# Nixie_Test.net
KiCad netlist of a schematic drawn in EAGLE
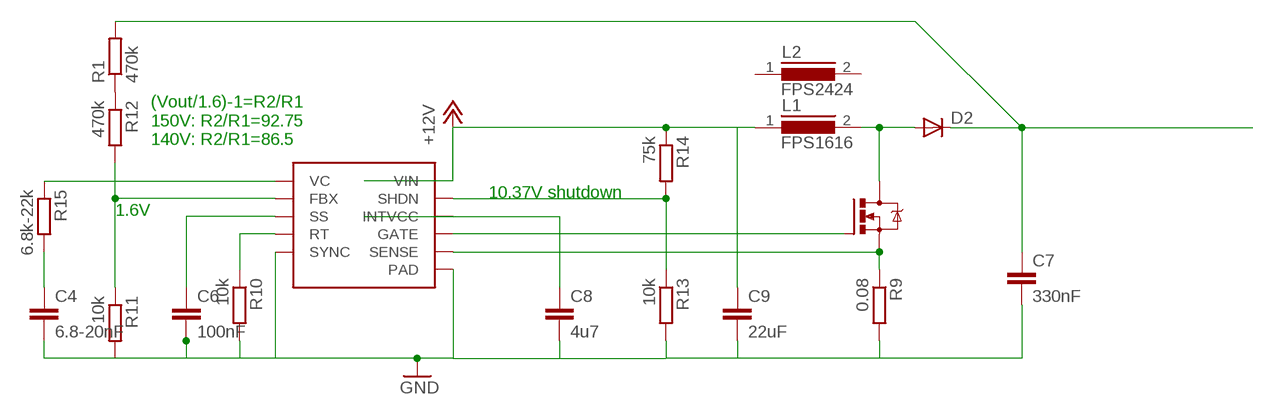
[diagram p0: schematic, sheet 1]
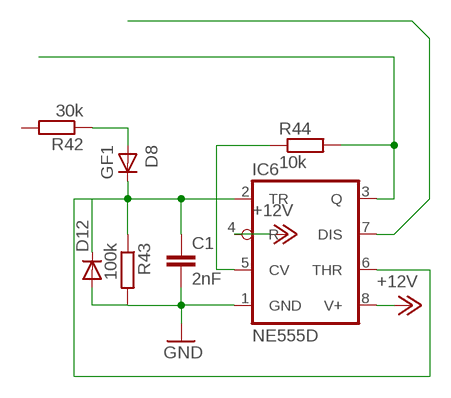
[diagram p1: schematic, sheet 2]
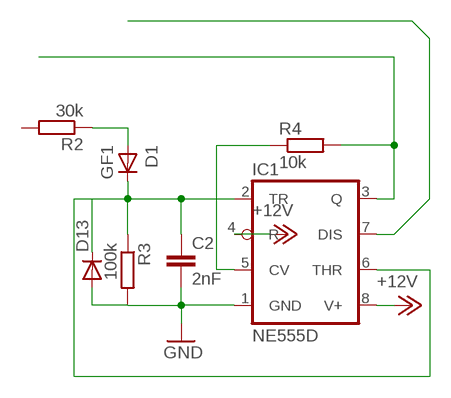
[diagram p2: schematic, sheet 3]
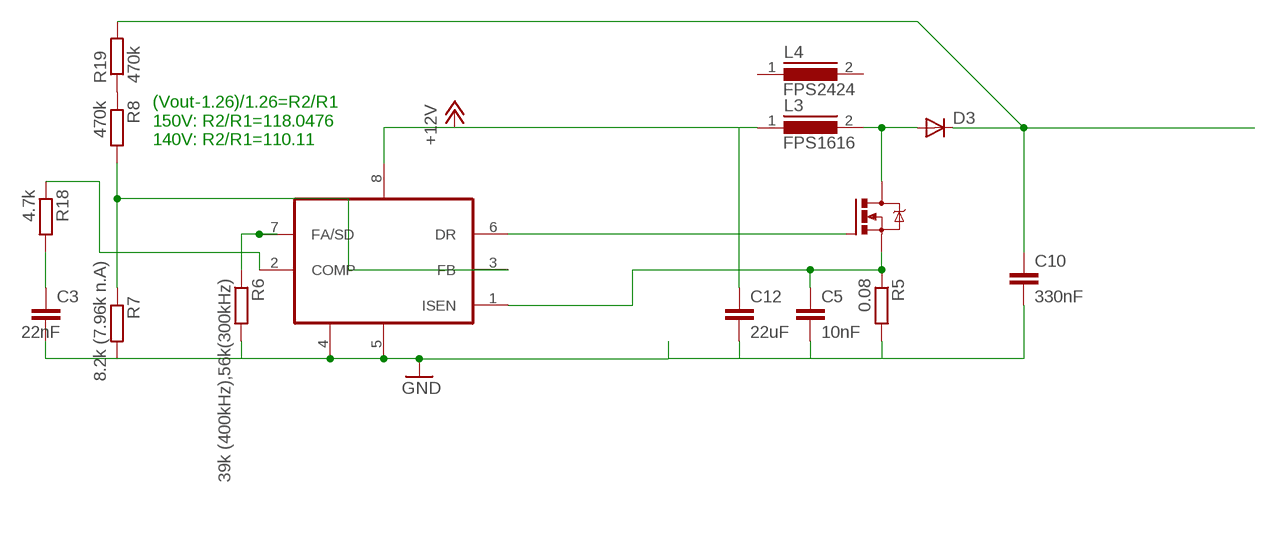
[diagram p3: schematic, sheet 4]
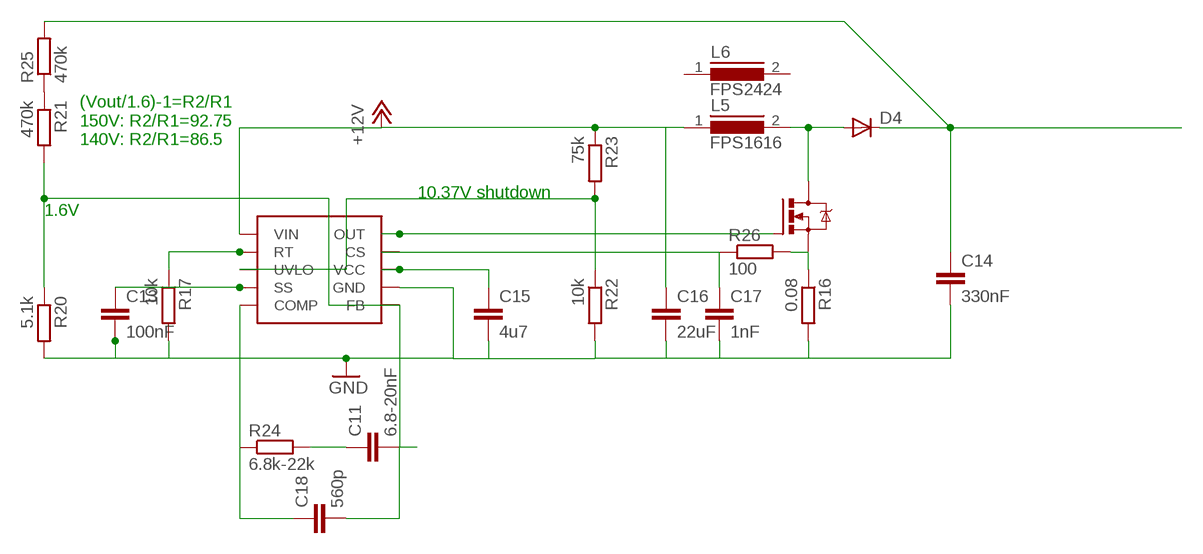
[diagram p4: schematic, sheet 5]
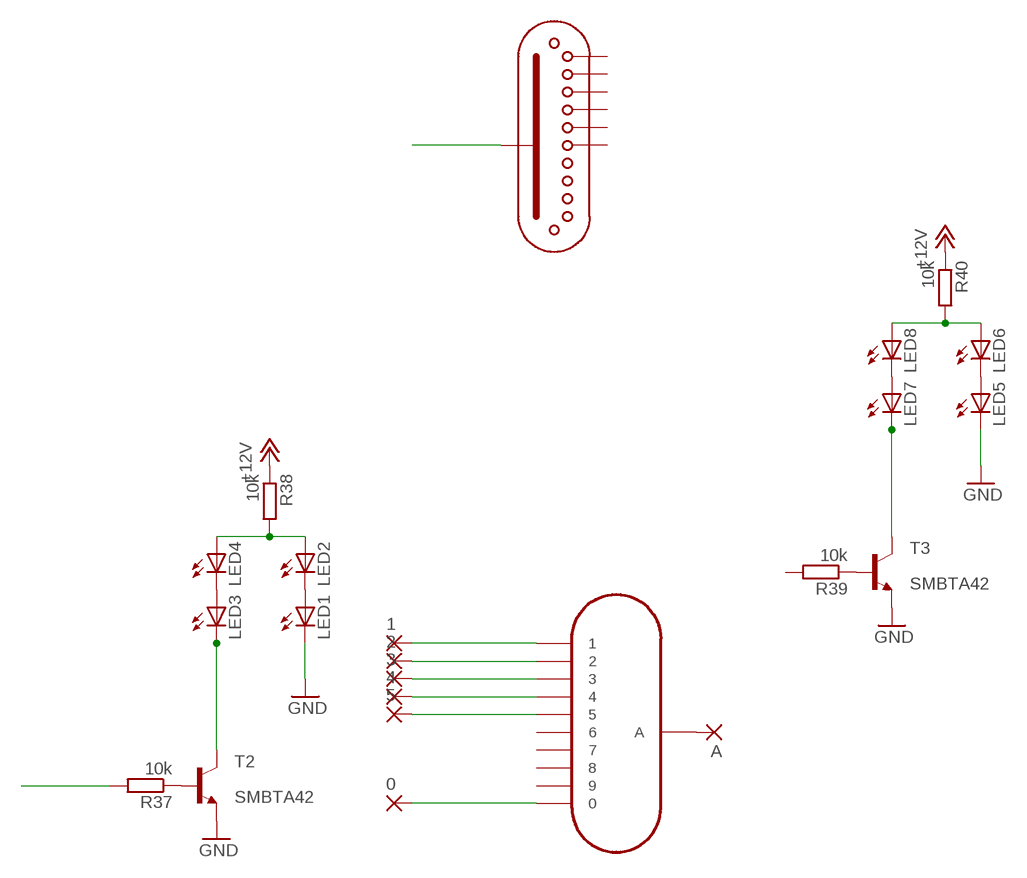
[diagram p5: schematic, sheet 6]
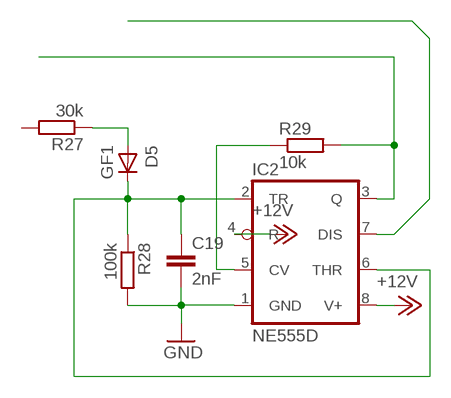
[diagram p6: schematic, sheet 7]
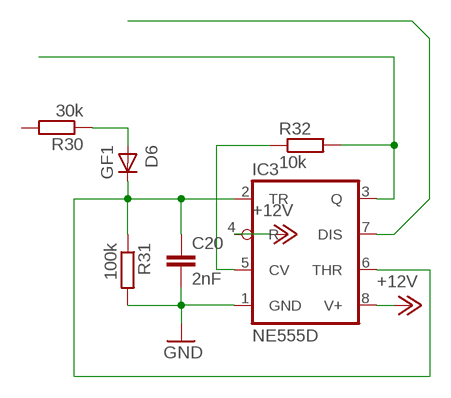
[diagram p7: schematic, sheet 8]
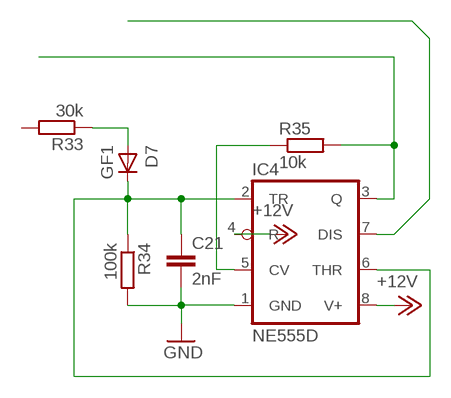
[diagram p8: schematic, sheet 9]
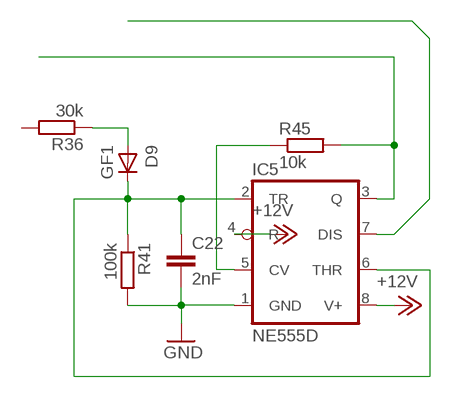
[diagram p9: schematic, sheet 10]
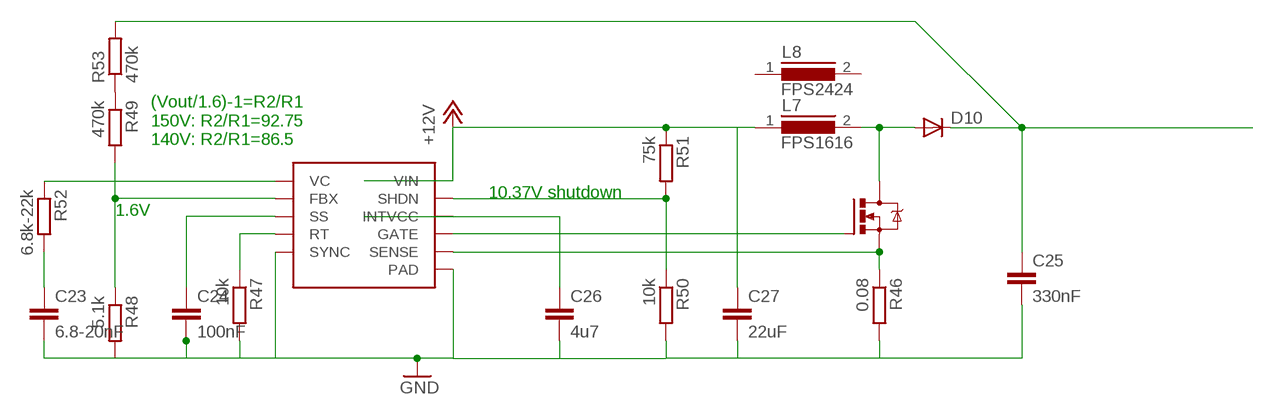
[diagram p10: schematic, sheet 11]
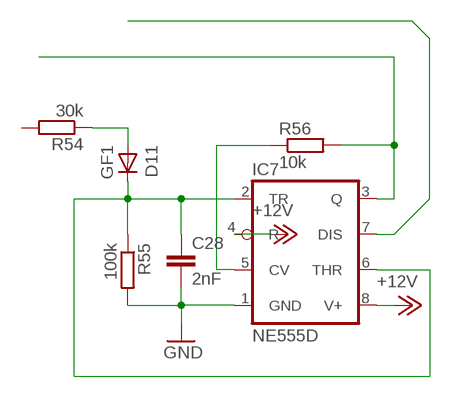
[diagram p11: schematic, sheet 12]
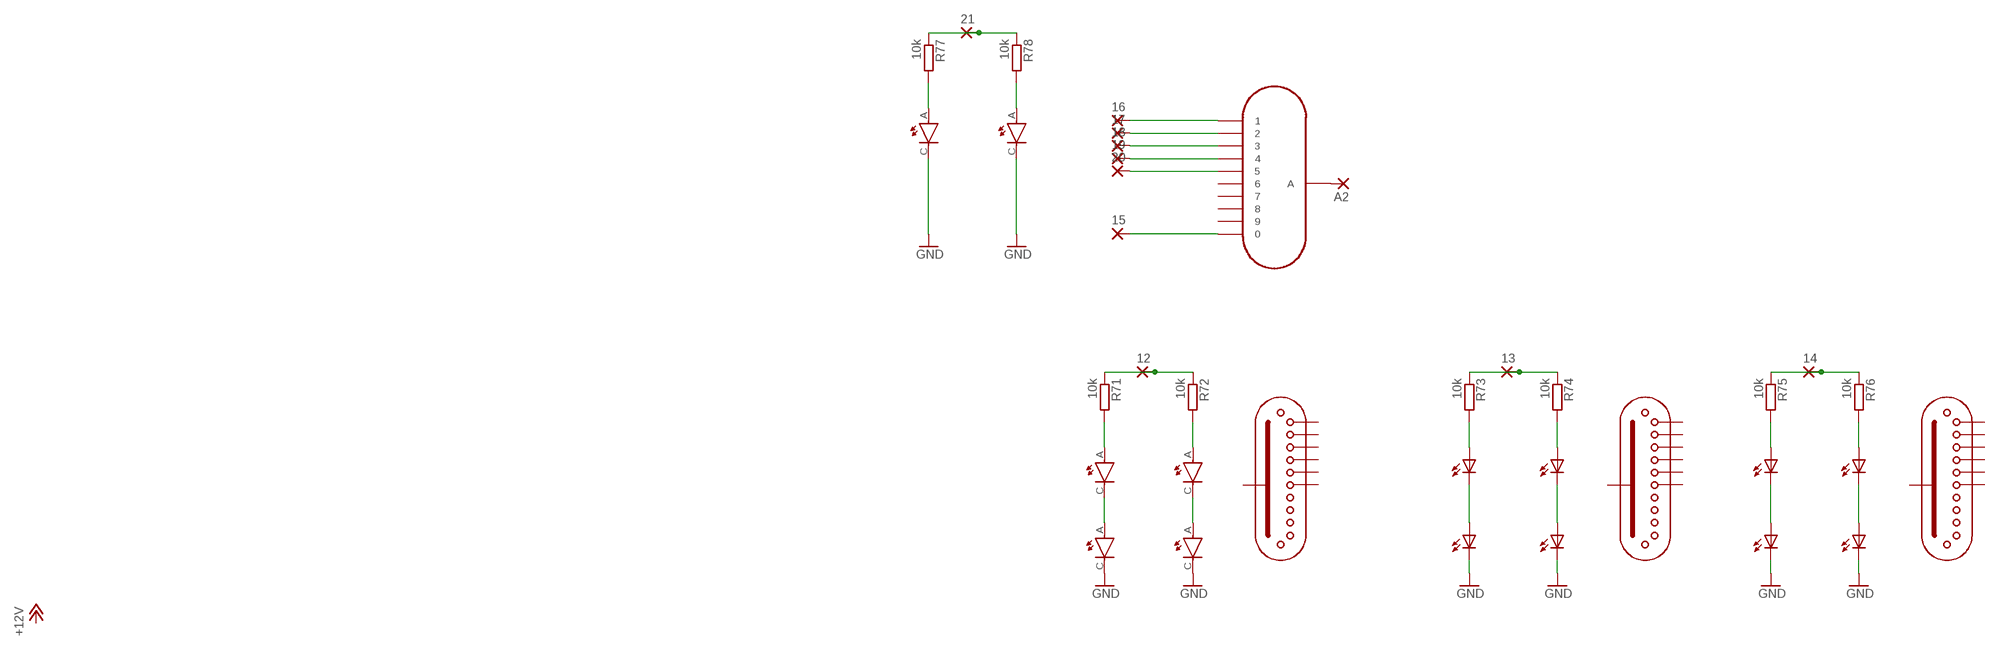
[diagram p12: schematic, sheet 13]
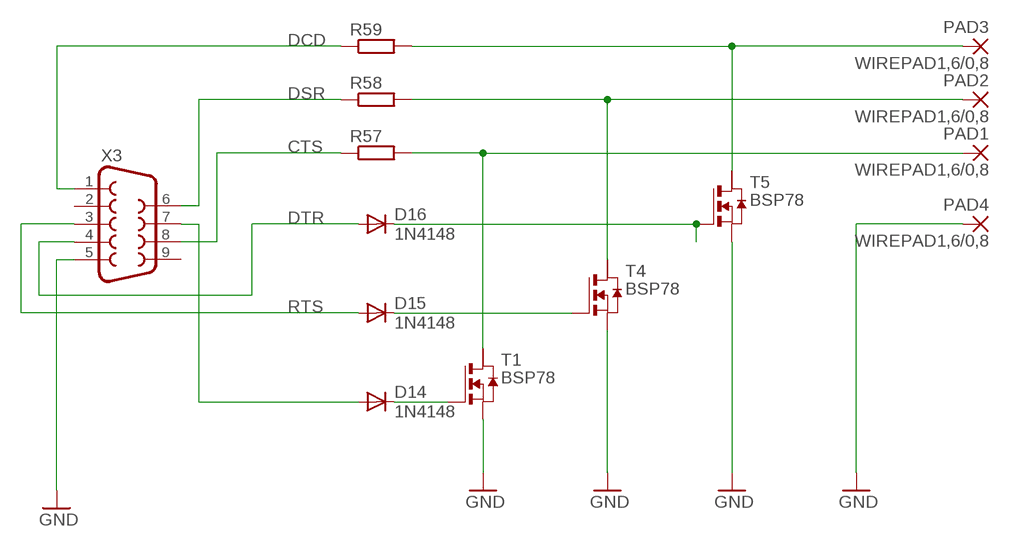
[diagram p13: schematic, sheet 14]
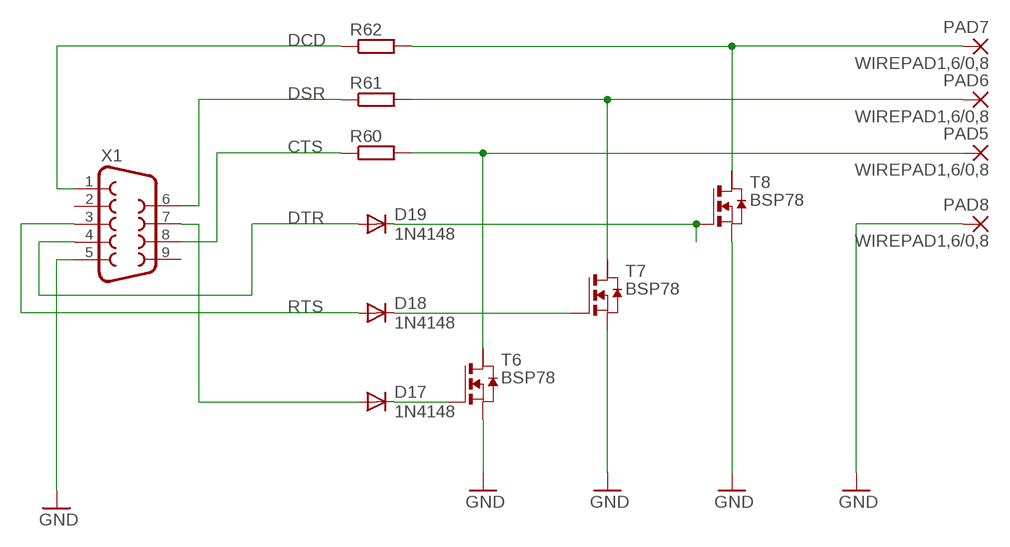
[diagram p14: schematic, sheet 15]
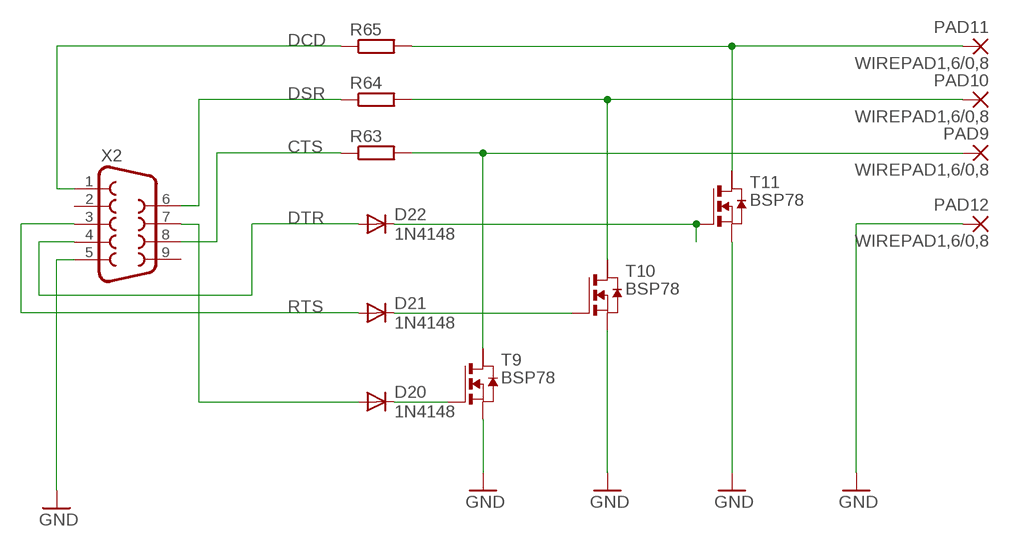
[diagram p15: schematic, sheet 16]
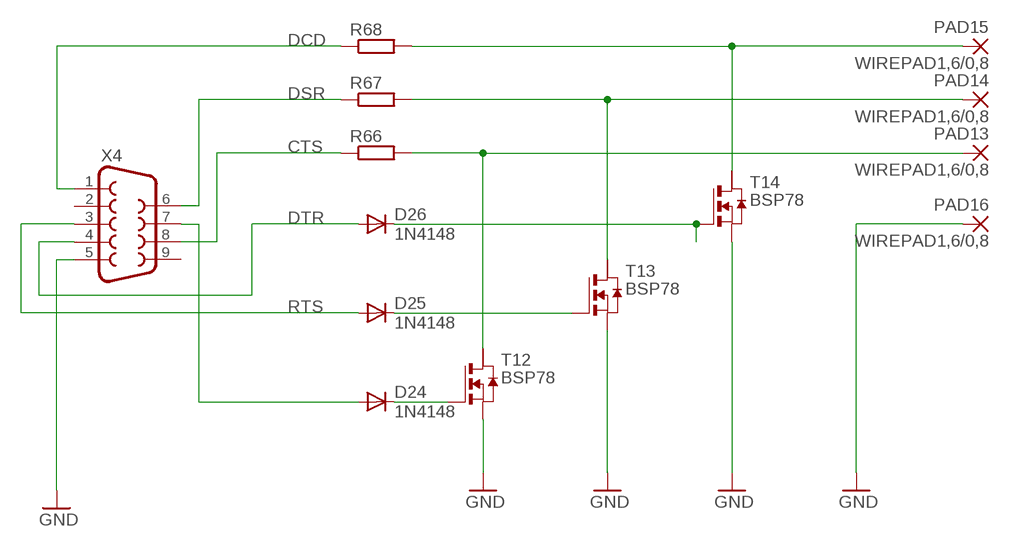
[diagram p16: schematic, sheet 17]

(export (version "E")
  (design (tool "Eeschema 10.0.6"))
  (components
    (comp (ref "C2")
      (value "2nF")
      (footprint "eagle-import:C1206K")
      (libsource (lib "eagle-import") (part "C-EUC1206K"))
    )
    (comp (ref "D1")
      (value "GF1")
      (footprint "eagle-import:SMA-DO214AC")
      (libsource (lib "eagle-import") (part "GF1"))
    )
    (comp (ref "D13")
      (value "DIODE-DO214AA")
      (footprint "eagle-import:DO214AA")
      (libsource (lib "eagle-import") (part "DIODE-DO214AA"))
    )
    (comp (ref "IC1")
      (value "NE555D")
      (footprint "eagle-import:SO08")
      (libsource (lib "eagle-import") (part "555DNE"))
    )
    (comp (ref "R2")
      (value "30k")
      (footprint "eagle-import:R0805")
      (libsource (lib "eagle-import") (part "R-EU_R0805"))
    )
    (comp (ref "R3")
      (value "100k")
      (footprint "eagle-import:R0805")
      (libsource (lib "eagle-import") (part "R-EU_R0805"))
    )
    (comp (ref "R4")
      (value "10k")
      (footprint "eagle-import:R0805")
      (libsource (lib "eagle-import") (part "R-EU_R0805"))
    )
    (comp (ref "C28")
      (value "2nF")
      (footprint "eagle-import:C1206K")
      (libsource (lib "eagle-import") (part "C-EUC1206K"))
    )
    (comp (ref "D11")
      (value "GF1")
      (footprint "eagle-import:SMA-DO214AC")
      (libsource (lib "eagle-import") (part "GF1"))
    )
    (comp (ref "IC7")
      (value "NE555D")
      (footprint "eagle-import:SO08")
      (libsource (lib "eagle-import") (part "555DNE"))
    )
    (comp (ref "R54")
      (value "30k")
      (footprint "eagle-import:R0805")
      (libsource (lib "eagle-import") (part "R-EU_R0805"))
    )
    (comp (ref "R55")
      (value "100k")
      (footprint "eagle-import:R0805")
      (libsource (lib "eagle-import") (part "R-EU_R0805"))
    )
    (comp (ref "R56")
      (value "10k")
      (footprint "eagle-import:R0805")
      (libsource (lib "eagle-import") (part "R-EU_R0805"))
    )
    (comp (ref "D14")
      (value "1N4148")
      (footprint "eagle-import:SOD323-W")
      (libsource (lib "eagle-import") (part "DIODE-SOD323-W"))
    )
    (comp (ref "D15")
      (value "1N4148")
      (footprint "eagle-import:SOD323-W")
      (libsource (lib "eagle-import") (part "DIODE-SOD323-W"))
    )
    (comp (ref "D16")
      (value "1N4148")
      (footprint "eagle-import:SOD323-W")
      (libsource (lib "eagle-import") (part "DIODE-SOD323-W"))
    )
    (comp (ref "PAD1")
      (value "WIREPAD1,6/0,8")
      (footprint "eagle-import:1,6_0,8")
      (libsource (lib "eagle-import") (part "WIREPAD1,6/0,8"))
    )
    (comp (ref "PAD2")
      (value "WIREPAD1,6/0,8")
      (footprint "eagle-import:1,6_0,8")
      (libsource (lib "eagle-import") (part "WIREPAD1,6/0,8"))
    )
    (comp (ref "PAD3")
      (value "WIREPAD1,6/0,8")
      (footprint "eagle-import:1,6_0,8")
      (libsource (lib "eagle-import") (part "WIREPAD1,6/0,8"))
    )
    (comp (ref "PAD4")
      (value "WIREPAD1,6/0,8")
      (footprint "eagle-import:1,6_0,8")
      (libsource (lib "eagle-import") (part "WIREPAD1,6/0,8"))
    )
    (comp (ref "R57")
      (value "R-EU_R0805")
      (footprint "eagle-import:R0805")
      (libsource (lib "eagle-import") (part "R-EU_R0805"))
    )
    (comp (ref "R58")
      (value "R-EU_R0805")
      (footprint "eagle-import:R0805")
      (libsource (lib "eagle-import") (part "R-EU_R0805"))
    )
    (comp (ref "R59")
      (value "R-EU_R0805")
      (footprint "eagle-import:R0805")
      (libsource (lib "eagle-import") (part "R-EU_R0805"))
    )
    (comp (ref "T1")
      (value "BSP78")
      (footprint "eagle-import:SOT223")
      (libsource (lib "eagle-import") (part "NMOSSOT223"))
    )
    (comp (ref "T4")
      (value "BSP78")
      (footprint "eagle-import:SOT223")
      (libsource (lib "eagle-import") (part "NMOSSOT223"))
    )
    (comp (ref "T5")
      (value "BSP78")
      (footprint "eagle-import:SOT223")
      (libsource (lib "eagle-import") (part "NMOSSOT223"))
    )
    (comp (ref "X3")
      (value "F09D")
      (footprint "eagle-import:F09D")
      (libsource (lib "eagle-import") (part "F09D"))
    )
    (comp (ref "12")
      (value "SMD2")
      (footprint "eagle-import:SMD1,27-2,54")
      (libsource (lib "eagle-import") (part "SMD2"))
    )
    (comp (ref "13")
      (value "SMD2")
      (footprint "eagle-import:SMD1,27-2,54")
      (libsource (lib "eagle-import") (part "SMD2"))
    )
    (comp (ref "14")
      (value "SMD2")
      (footprint "eagle-import:SMD1,27-2,54")
      (libsource (lib "eagle-import") (part "SMD2"))
    )
    (comp (ref "15")
      (value "SMD2")
      (footprint "eagle-import:SMD1,27-2,54")
      (libsource (lib "eagle-import") (part "SMD2"))
    )
    (comp (ref "16")
      (value "SMD2")
      (footprint "eagle-import:SMD1,27-2,54")
      (libsource (lib "eagle-import") (part "SMD2"))
    )
    (comp (ref "17")
      (value "SMD2")
      (footprint "eagle-import:SMD1,27-2,54")
      (libsource (lib "eagle-import") (part "SMD2"))
    )
    (comp (ref "18")
      (value "SMD2")
      (footprint "eagle-import:SMD1,27-2,54")
      (libsource (lib "eagle-import") (part "SMD2"))
    )
    (comp (ref "19")
      (value "SMD2")
      (footprint "eagle-import:SMD1,27-2,54")
      (libsource (lib "eagle-import") (part "SMD2"))
    )
    (comp (ref "20")
      (value "SMD2")
      (footprint "eagle-import:SMD1,27-2,54")
      (libsource (lib "eagle-import") (part "SMD2"))
    )
    (comp (ref "21")
      (value "SMD2")
      (footprint "eagle-import:SMD1,27-2,54")
      (libsource (lib "eagle-import") (part "SMD2"))
    )
    (comp (ref "A2")
      (value "SMD2")
      (footprint "eagle-import:SMD1,27-2,54")
      (libsource (lib "eagle-import") (part "SMD2"))
    )
    (comp (ref "LED17")
      (value "LED_PLCC6")
      (footprint "eagle-import:PLCC6")
      (libsource (lib "eagle-import") (part "LED_PLCC6"))
    )
    (comp (ref "LED18")
      (value "LED_PLCC6")
      (footprint "eagle-import:PLCC6")
      (libsource (lib "eagle-import") (part "LED_PLCC6"))
    )
    (comp (ref "LED19")
      (value "LED_PLCC6")
      (footprint "eagle-import:PLCC6")
      (libsource (lib "eagle-import") (part "LED_PLCC6"))
    )
    (comp (ref "LED20")
      (value "LED_PLCC6")
      (footprint "eagle-import:PLCC6")
      (libsource (lib "eagle-import") (part "LED_PLCC6"))
    )
    (comp (ref "LED21")
      (value "LED_LRTB_G6TG")
      (footprint "eagle-import:PLCC6")
      (libsource (lib "eagle-import") (part "LED_LRTB_G6TG"))
    )
    (comp (ref "LED22")
      (value "LED_LRTB_G6TG")
      (footprint "eagle-import:PLCC6")
      (libsource (lib "eagle-import") (part "LED_LRTB_G6TG"))
    )
    (comp (ref "N3")
      (value "IN-12A-IN-12")
      (footprint "eagle-import:IN-12")
      (libsource (lib "eagle-import") (part "IN-12A-IN-12"))
    )
    (comp (ref "R71")
      (value "10k")
      (footprint "eagle-import:R0805")
      (libsource (lib "eagle-import") (part "R-EU_R0805"))
    )
    (comp (ref "R72")
      (value "10k")
      (footprint "eagle-import:R0805")
      (libsource (lib "eagle-import") (part "R-EU_R0805"))
    )
    (comp (ref "R73")
      (value "10k")
      (footprint "eagle-import:R0805")
      (libsource (lib "eagle-import") (part "R-EU_R0805"))
    )
    (comp (ref "R74")
      (value "10k")
      (footprint "eagle-import:R0805")
      (libsource (lib "eagle-import") (part "R-EU_R0805"))
    )
    (comp (ref "R75")
      (value "10k")
      (footprint "eagle-import:R0805")
      (libsource (lib "eagle-import") (part "R-EU_R0805"))
    )
    (comp (ref "R76")
      (value "10k")
      (footprint "eagle-import:R0805")
      (libsource (lib "eagle-import") (part "R-EU_R0805"))
    )
    (comp (ref "R77")
      (value "10k")
      (footprint "eagle-import:R0805")
      (libsource (lib "eagle-import") (part "R-EU_R0805"))
    )
    (comp (ref "R78")
      (value "10k")
      (footprint "eagle-import:R0805")
      (libsource (lib "eagle-import") (part "R-EU_R0805"))
    )
    (comp (ref "U$5")
      (value "PLCC2")
      (footprint "eagle-import:PLCC2")
      (libsource (lib "eagle-import") (part "PLCC2"))
    )
    (comp (ref "U$6")
      (value "PLCC2")
      (footprint "eagle-import:PLCC2")
      (libsource (lib "eagle-import") (part "PLCC2"))
    )
    (comp (ref "U$7")
      (value "ZM1020")
      (footprint "eagle-import:ZM1020")
      (libsource (lib "eagle-import") (part "ZM1020"))
    )
    (comp (ref "U$8")
      (value "PLCC2")
      (footprint "eagle-import:PLCC2")
      (libsource (lib "eagle-import") (part "PLCC2"))
    )
    (comp (ref "U$9")
      (value "PLCC2")
      (footprint "eagle-import:PLCC2")
      (libsource (lib "eagle-import") (part "PLCC2"))
    )
    (comp (ref "U$10")
      (value "ZM1020")
      (footprint "eagle-import:ZM1020")
      (libsource (lib "eagle-import") (part "ZM1020"))
    )
    (comp (ref "U$11")
      (value "ZM1020")
      (footprint "eagle-import:ZM1020")
      (libsource (lib "eagle-import") (part "ZM1020"))
    )
    (comp (ref "U$12")
      (value "PLCC2")
      (footprint "eagle-import:PLCC2")
      (libsource (lib "eagle-import") (part "PLCC2"))
    )
    (comp (ref "U$13")
      (value "PLCC2")
      (footprint "eagle-import:PLCC2")
      (libsource (lib "eagle-import") (part "PLCC2"))
    )
    (comp (ref "C21")
      (value "2nF")
      (footprint "eagle-import:C1206K")
      (libsource (lib "eagle-import") (part "C-EUC1206K"))
    )
    (comp (ref "D7")
      (value "GF1")
      (footprint "eagle-import:SMA-DO214AC")
      (libsource (lib "eagle-import") (part "GF1"))
    )
    (comp (ref "IC4")
      (value "NE555D")
      (footprint "eagle-import:SO08")
      (libsource (lib "eagle-import") (part "555DNE"))
    )
    (comp (ref "R33")
      (value "30k")
      (footprint "eagle-import:R0805")
      (libsource (lib "eagle-import") (part "R-EU_R0805"))
    )
    (comp (ref "R34")
      (value "100k")
      (footprint "eagle-import:R0805")
      (libsource (lib "eagle-import") (part "R-EU_R0805"))
    )
    (comp (ref "R35")
      (value "10k")
      (footprint "eagle-import:R0805")
      (libsource (lib "eagle-import") (part "R-EU_R0805"))
    )
    (comp (ref "C1")
      (value "2nF")
      (footprint "eagle-import:C1206K")
      (libsource (lib "eagle-import") (part "C-EUC1206K"))
    )
    (comp (ref "D8")
      (value "GF1")
      (footprint "eagle-import:SMA-DO214AC")
      (libsource (lib "eagle-import") (part "GF1"))
    )
    (comp (ref "D12")
      (value "DIODE-DO214AA")
      (footprint "eagle-import:DO214AA")
      (libsource (lib "eagle-import") (part "DIODE-DO214AA"))
    )
    (comp (ref "IC6")
      (value "NE555D")
      (footprint "eagle-import:SO08")
      (libsource (lib "eagle-import") (part "555DNE"))
    )
    (comp (ref "R42")
      (value "30k")
      (footprint "eagle-import:R0805")
      (libsource (lib "eagle-import") (part "R-EU_R0805"))
    )
    (comp (ref "R43")
      (value "100k")
      (footprint "eagle-import:R0805")
      (libsource (lib "eagle-import") (part "R-EU_R0805"))
    )
    (comp (ref "R44")
      (value "10k")
      (footprint "eagle-import:R0805")
      (libsource (lib "eagle-import") (part "R-EU_R0805"))
    )
    (comp (ref "C4")
      (value "6.8-20nF")
      (footprint "eagle-import:C0805K")
      (libsource (lib "eagle-import") (part "C-EUC0805K"))
    )
    (comp (ref "C6")
      (value "100nF")
      (footprint "eagle-import:C0805K")
      (libsource (lib "eagle-import") (part "C-EUC0805K"))
    )
    (comp (ref "C7")
      (value "330nF")
      (footprint "eagle-import:C1812")
      (libsource (lib "eagle-import") (part "C-EUC1812"))
    )
    (comp (ref "C8")
      (value "4u7")
      (footprint "eagle-import:C1206K")
      (libsource (lib "eagle-import") (part "C-EUC1206K"))
    )
    (comp (ref "C9")
      (value "22uF")
      (footprint "eagle-import:C1210K")
      (libsource (lib "eagle-import") (part "C-EUC1210K"))
    )
    (comp (ref "D2")
      (value "DIODE-DO219AB")
      (footprint "eagle-import:DO219AB")
      (libsource (lib "eagle-import") (part "DIODE-DO219AB"))
    )
    (comp (ref "L1")
      (value "FPS1616")
      (footprint "eagle-import:1616FPS_22UH")
      (libsource (lib "eagle-import") (part "FPS1616"))
    )
    (comp (ref "L2")
      (value "FPS2424")
      (footprint "eagle-import:242408FPS_22UH")
      (libsource (lib "eagle-import") (part "FPS2424"))
    )
    (comp (ref "Q1")
      (value "N-MOSFET-TO252-DPAK")
      (footprint "eagle-import:TO252")
      (libsource (lib "eagle-import") (part "N-MOSFET-TO252-DPAK"))
    )
    (comp (ref "R1")
      (value "470k")
      (footprint "eagle-import:R0805")
      (libsource (lib "eagle-import") (part "R-EU_R0805"))
    )
    (comp (ref "R9")
      (value "0.08")
      (footprint "eagle-import:R0805")
      (libsource (lib "eagle-import") (part "R-EU_R0805"))
    )
    (comp (ref "R10")
      (value "10k")
      (footprint "eagle-import:R0805")
      (libsource (lib "eagle-import") (part "R-EU_R0805"))
    )
    (comp (ref "R11")
      (value "10k")
      (footprint "eagle-import:R0805")
      (libsource (lib "eagle-import") (part "R-EU_R0805"))
    )
    (comp (ref "R12")
      (value "470k")
      (footprint "eagle-import:R0805")
      (libsource (lib "eagle-import") (part "R-EU_R0805"))
    )
    (comp (ref "R13")
      (value "10k")
      (footprint "eagle-import:R0805")
      (libsource (lib "eagle-import") (part "R-EU_R0805"))
    )
    (comp (ref "R14")
      (value "75k")
      (footprint "eagle-import:R0805")
      (libsource (lib "eagle-import") (part "R-EU_R0805"))
    )
    (comp (ref "R15")
      (value "6.8k-22k")
      (footprint "eagle-import:R0805")
      (libsource (lib "eagle-import") (part "R-EU_R0805"))
    )
    (comp (ref "U2")
      (value "LT3757MSOP-10")
      (footprint "eagle-import:MSOP-10")
      (libsource (lib "eagle-import") (part "LT3757MSOP-10"))
    )
    (comp (ref "D17")
      (value "1N4148")
      (footprint "eagle-import:SOD323-W")
      (libsource (lib "eagle-import") (part "DIODE-SOD323-W"))
    )
    (comp (ref "D18")
      (value "1N4148")
      (footprint "eagle-import:SOD323-W")
      (libsource (lib "eagle-import") (part "DIODE-SOD323-W"))
    )
    (comp (ref "D19")
      (value "1N4148")
      (footprint "eagle-import:SOD323-W")
      (libsource (lib "eagle-import") (part "DIODE-SOD323-W"))
    )
    (comp (ref "PAD5")
      (value "WIREPAD1,6/0,8")
      (footprint "eagle-import:1,6_0,8")
      (libsource (lib "eagle-import") (part "WIREPAD1,6/0,8"))
    )
    (comp (ref "PAD6")
      (value "WIREPAD1,6/0,8")
      (footprint "eagle-import:1,6_0,8")
      (libsource (lib "eagle-import") (part "WIREPAD1,6/0,8"))
    )
    (comp (ref "PAD7")
      (value "WIREPAD1,6/0,8")
      (footprint "eagle-import:1,6_0,8")
      (libsource (lib "eagle-import") (part "WIREPAD1,6/0,8"))
    )
    (comp (ref "PAD8")
      (value "WIREPAD1,6/0,8")
      (footprint "eagle-import:1,6_0,8")
      (libsource (lib "eagle-import") (part "WIREPAD1,6/0,8"))
    )
    (comp (ref "R60")
      (value "R-EU_R0805")
      (footprint "eagle-import:R0805")
      (libsource (lib "eagle-import") (part "R-EU_R0805"))
    )
    (comp (ref "R61")
      (value "R-EU_R0805")
      (footprint "eagle-import:R0805")
      (libsource (lib "eagle-import") (part "R-EU_R0805"))
    )
    (comp (ref "R62")
      (value "R-EU_R0805")
      (footprint "eagle-import:R0805")
      (libsource (lib "eagle-import") (part "R-EU_R0805"))
    )
    (comp (ref "T6")
      (value "BSP78")
      (footprint "eagle-import:SOT223")
      (libsource (lib "eagle-import") (part "NMOSSOT223"))
    )
    (comp (ref "T7")
      (value "BSP78")
      (footprint "eagle-import:SOT223")
      (libsource (lib "eagle-import") (part "NMOSSOT223"))
    )
    (comp (ref "T8")
      (value "BSP78")
      (footprint "eagle-import:SOT223")
      (libsource (lib "eagle-import") (part "NMOSSOT223"))
    )
    (comp (ref "X1")
      (value "F09D")
      (footprint "eagle-import:F09D")
      (libsource (lib "eagle-import") (part "F09D"))
    )
    (comp (ref "D24")
      (value "1N4148")
      (footprint "eagle-import:SOD323-W")
      (libsource (lib "eagle-import") (part "DIODE-SOD323-W"))
    )
    (comp (ref "D25")
      (value "1N4148")
      (footprint "eagle-import:SOD323-W")
      (libsource (lib "eagle-import") (part "DIODE-SOD323-W"))
    )
    (comp (ref "D26")
      (value "1N4148")
      (footprint "eagle-import:SOD323-W")
      (libsource (lib "eagle-import") (part "DIODE-SOD323-W"))
    )
    (comp (ref "PAD13")
      (value "WIREPAD1,6/0,8")
      (footprint "eagle-import:1,6_0,8")
      (libsource (lib "eagle-import") (part "WIREPAD1,6/0,8"))
    )
    (comp (ref "PAD14")
      (value "WIREPAD1,6/0,8")
      (footprint "eagle-import:1,6_0,8")
      (libsource (lib "eagle-import") (part "WIREPAD1,6/0,8"))
    )
    (comp (ref "PAD15")
      (value "WIREPAD1,6/0,8")
      (footprint "eagle-import:1,6_0,8")
      (libsource (lib "eagle-import") (part "WIREPAD1,6/0,8"))
    )
    (comp (ref "PAD16")
      (value "WIREPAD1,6/0,8")
      (footprint "eagle-import:1,6_0,8")
      (libsource (lib "eagle-import") (part "WIREPAD1,6/0,8"))
    )
    (comp (ref "R66")
      (value "R-EU_R0805")
      (footprint "eagle-import:R0805")
      (libsource (lib "eagle-import") (part "R-EU_R0805"))
    )
    (comp (ref "R67")
      (value "R-EU_R0805")
      (footprint "eagle-import:R0805")
      (libsource (lib "eagle-import") (part "R-EU_R0805"))
    )
    (comp (ref "R68")
      (value "R-EU_R0805")
      (footprint "eagle-import:R0805")
      (libsource (lib "eagle-import") (part "R-EU_R0805"))
    )
    (comp (ref "T12")
      (value "BSP78")
      (footprint "eagle-import:SOT223")
      (libsource (lib "eagle-import") (part "NMOSSOT223"))
    )
    (comp (ref "T13")
      (value "BSP78")
      (footprint "eagle-import:SOT223")
      (libsource (lib "eagle-import") (part "NMOSSOT223"))
    )
    (comp (ref "T14")
      (value "BSP78")
      (footprint "eagle-import:SOT223")
      (libsource (lib "eagle-import") (part "NMOSSOT223"))
    )
    (comp (ref "X4")
      (value "F09D")
      (footprint "eagle-import:F09D")
      (libsource (lib "eagle-import") (part "F09D"))
    )
    (comp (ref "C23")
      (value "6.8-20nF")
      (footprint "eagle-import:C0805K")
      (libsource (lib "eagle-import") (part "C-EUC0805K"))
    )
    (comp (ref "C24")
      (value "100nF")
      (footprint "eagle-import:C0805K")
      (libsource (lib "eagle-import") (part "C-EUC0805K"))
    )
    (comp (ref "C25")
      (value "330nF")
      (footprint "eagle-import:C1812")
      (libsource (lib "eagle-import") (part "C-EUC1812"))
    )
    (comp (ref "C26")
      (value "4u7")
      (footprint "eagle-import:C1206K")
      (libsource (lib "eagle-import") (part "C-EUC1206K"))
    )
    (comp (ref "C27")
      (value "22uF")
      (footprint "eagle-import:C1210K")
      (libsource (lib "eagle-import") (part "C-EUC1210K"))
    )
    (comp (ref "D10")
      (value "DIODE-DO219AB")
      (footprint "eagle-import:DO219AB")
      (libsource (lib "eagle-import") (part "DIODE-DO219AB"))
    )
    (comp (ref "L7")
      (value "FPS1616")
      (footprint "eagle-import:1616FPS_22UH")
      (libsource (lib "eagle-import") (part "FPS1616"))
    )
    (comp (ref "L8")
      (value "FPS2424")
      (footprint "eagle-import:242408FPS_22UH")
      (libsource (lib "eagle-import") (part "FPS2424"))
    )
    (comp (ref "Q4")
      (value "N-MOSFET-TO252-DPAK")
      (footprint "eagle-import:TO252")
      (libsource (lib "eagle-import") (part "N-MOSFET-TO252-DPAK"))
    )
    (comp (ref "R46")
      (value "0.08")
      (footprint "eagle-import:R0805")
      (libsource (lib "eagle-import") (part "R-EU_R0805"))
    )
    (comp (ref "R47")
      (value "10k")
      (footprint "eagle-import:R0805")
      (libsource (lib "eagle-import") (part "R-EU_R0805"))
    )
    (comp (ref "R48")
      (value "5.1k")
      (footprint "eagle-import:R0805")
      (libsource (lib "eagle-import") (part "R-EU_R0805"))
    )
    (comp (ref "R49")
      (value "470k")
      (footprint "eagle-import:R0805")
      (libsource (lib "eagle-import") (part "R-EU_R0805"))
    )
    (comp (ref "R50")
      (value "10k")
      (footprint "eagle-import:R0805")
      (libsource (lib "eagle-import") (part "R-EU_R0805"))
    )
    (comp (ref "R51")
      (value "75k")
      (footprint "eagle-import:R0805")
      (libsource (lib "eagle-import") (part "R-EU_R0805"))
    )
    (comp (ref "R52")
      (value "6.8k-22k")
      (footprint "eagle-import:R0805")
      (libsource (lib "eagle-import") (part "R-EU_R0805"))
    )
    (comp (ref "R53")
      (value "470k")
      (footprint "eagle-import:R0805")
      (libsource (lib "eagle-import") (part "R-EU_R0805"))
    )
    (comp (ref "U1")
      (value "LT3757MSOP-10")
      (footprint "eagle-import:MSOP-10")
      (libsource (lib "eagle-import") (part "LT3757MSOP-10"))
    )
    (comp (ref "C20")
      (value "2nF")
      (footprint "eagle-import:C1206K")
      (libsource (lib "eagle-import") (part "C-EUC1206K"))
    )
    (comp (ref "D6")
      (value "GF1")
      (footprint "eagle-import:SMA-DO214AC")
      (libsource (lib "eagle-import") (part "GF1"))
    )
    (comp (ref "IC3")
      (value "NE555D")
      (footprint "eagle-import:SO08")
      (libsource (lib "eagle-import") (part "555DNE"))
    )
    (comp (ref "R30")
      (value "30k")
      (footprint "eagle-import:R0805")
      (libsource (lib "eagle-import") (part "R-EU_R0805"))
    )
    (comp (ref "R31")
      (value "100k")
      (footprint "eagle-import:R0805")
      (libsource (lib "eagle-import") (part "R-EU_R0805"))
    )
    (comp (ref "R32")
      (value "10k")
      (footprint "eagle-import:R0805")
      (libsource (lib "eagle-import") (part "R-EU_R0805"))
    )
    (comp (ref "C22")
      (value "2nF")
      (footprint "eagle-import:C1206K")
      (libsource (lib "eagle-import") (part "C-EUC1206K"))
    )
    (comp (ref "D9")
      (value "GF1")
      (footprint "eagle-import:SMA-DO214AC")
      (libsource (lib "eagle-import") (part "GF1"))
    )
    (comp (ref "IC5")
      (value "NE555D")
      (footprint "eagle-import:SO08")
      (libsource (lib "eagle-import") (part "555DNE"))
    )
    (comp (ref "R36")
      (value "30k")
      (footprint "eagle-import:R0805")
      (libsource (lib "eagle-import") (part "R-EU_R0805"))
    )
    (comp (ref "R41")
      (value "100k")
      (footprint "eagle-import:R0805")
      (libsource (lib "eagle-import") (part "R-EU_R0805"))
    )
    (comp (ref "R45")
      (value "10k")
      (footprint "eagle-import:R0805")
      (libsource (lib "eagle-import") (part "R-EU_R0805"))
    )
    (comp (ref "C3")
      (value "22nF")
      (footprint "eagle-import:C0805K")
      (libsource (lib "eagle-import") (part "C-EUC0805K"))
    )
    (comp (ref "C5")
      (value "10nF")
      (footprint "eagle-import:C0805K")
      (libsource (lib "eagle-import") (part "C-EUC0805K"))
    )
    (comp (ref "C10")
      (value "330nF")
      (footprint "eagle-import:C1812")
      (libsource (lib "eagle-import") (part "C-EUC1812"))
    )
    (comp (ref "C12")
      (value "22uF")
      (footprint "eagle-import:C1210K")
      (libsource (lib "eagle-import") (part "C-EUC1210K"))
    )
    (comp (ref "D3")
      (value "DIODE-DO219AB")
      (footprint "eagle-import:DO219AB")
      (libsource (lib "eagle-import") (part "DIODE-DO219AB"))
    )
    (comp (ref "L3")
      (value "FPS1616")
      (footprint "eagle-import:1616FPS_22UH")
      (libsource (lib "eagle-import") (part "FPS1616"))
    )
    (comp (ref "L4")
      (value "FPS2424")
      (footprint "eagle-import:242408FPS_22UH")
      (libsource (lib "eagle-import") (part "FPS2424"))
    )
    (comp (ref "Q2")
      (value "N-MOSFET-TO252-DPAK")
      (footprint "eagle-import:TO252")
      (libsource (lib "eagle-import") (part "N-MOSFET-TO252-DPAK"))
    )
    (comp (ref "R5")
      (value "0.08")
      (footprint "eagle-import:R0805")
      (libsource (lib "eagle-import") (part "R-EU_R0805"))
    )
    (comp (ref "R6")
      (value "39k (400kHz),56k(300kHz)")
      (footprint "eagle-import:R0805")
      (libsource (lib "eagle-import") (part "R-EU_R0805"))
    )
    (comp (ref "R7")
      (value "8.2k (7.96k n.A)")
      (footprint "eagle-import:R0805")
      (libsource (lib "eagle-import") (part "R-EU_R0805"))
    )
    (comp (ref "R8")
      (value "470k")
      (footprint "eagle-import:R0805")
      (libsource (lib "eagle-import") (part "R-EU_R0805"))
    )
    (comp (ref "R18")
      (value "4.7k")
      (footprint "eagle-import:R0805")
      (libsource (lib "eagle-import") (part "R-EU_R0805"))
    )
    (comp (ref "R19")
      (value "470k")
      (footprint "eagle-import:R0805")
      (libsource (lib "eagle-import") (part "R-EU_R0805"))
    )
    (comp (ref "U3")
      (value "LM3478")
      (footprint "eagle-import:MSOP08")
      (libsource (lib "eagle-import") (part "LM3478"))
    )
    (comp (ref "C11")
      (value "6.8-20nF")
      (footprint "eagle-import:C0805K")
      (libsource (lib "eagle-import") (part "C-EUC0805K"))
    )
    (comp (ref "C13")
      (value "100nF")
      (footprint "eagle-import:C0805K")
      (libsource (lib "eagle-import") (part "C-EUC0805K"))
    )
    (comp (ref "C14")
      (value "330nF")
      (footprint "eagle-import:C1812")
      (libsource (lib "eagle-import") (part "C-EUC1812"))
    )
    (comp (ref "C15")
      (value "4u7")
      (footprint "eagle-import:C1206K")
      (libsource (lib "eagle-import") (part "C-EUC1206K"))
    )
    (comp (ref "C16")
      (value "22uF")
      (footprint "eagle-import:C1210K")
      (libsource (lib "eagle-import") (part "C-EUC1210K"))
    )
    (comp (ref "C17")
      (value "1nF")
      (footprint "eagle-import:C0805K")
      (libsource (lib "eagle-import") (part "C-EUC0805K"))
    )
    (comp (ref "C18")
      (value "560p")
      (footprint "eagle-import:C0805K")
      (libsource (lib "eagle-import") (part "C-EUC0805K"))
    )
    (comp (ref "D4")
      (value "DIODE-DO219AB")
      (footprint "eagle-import:DO219AB")
      (libsource (lib "eagle-import") (part "DIODE-DO219AB"))
    )
    (comp (ref "L5")
      (value "FPS1616")
      (footprint "eagle-import:1616FPS_22UH")
      (libsource (lib "eagle-import") (part "FPS1616"))
    )
    (comp (ref "L6")
      (value "FPS2424")
      (footprint "eagle-import:242408FPS_22UH")
      (libsource (lib "eagle-import") (part "FPS2424"))
    )
    (comp (ref "Q3")
      (value "N-MOSFET-TO252-DPAK")
      (footprint "eagle-import:TO252")
      (libsource (lib "eagle-import") (part "N-MOSFET-TO252-DPAK"))
    )
    (comp (ref "R16")
      (value "0.08")
      (footprint "eagle-import:R0805")
      (libsource (lib "eagle-import") (part "R-EU_R0805"))
    )
    (comp (ref "R17")
      (value "10k")
      (footprint "eagle-import:R0805")
      (libsource (lib "eagle-import") (part "R-EU_R0805"))
    )
    (comp (ref "R20")
      (value "5.1k")
      (footprint "eagle-import:R0805")
      (libsource (lib "eagle-import") (part "R-EU_R0805"))
    )
    (comp (ref "R21")
      (value "470k")
      (footprint "eagle-import:R0805")
      (libsource (lib "eagle-import") (part "R-EU_R0805"))
    )
    (comp (ref "R22")
      (value "10k")
      (footprint "eagle-import:R0805")
      (libsource (lib "eagle-import") (part "R-EU_R0805"))
    )
    (comp (ref "R23")
      (value "75k")
      (footprint "eagle-import:R0805")
      (libsource (lib "eagle-import") (part "R-EU_R0805"))
    )
    (comp (ref "R24")
      (value "6.8k-22k")
      (footprint "eagle-import:R0805")
      (libsource (lib "eagle-import") (part "R-EU_R0805"))
    )
    (comp (ref "R25")
      (value "470k")
      (footprint "eagle-import:R0805")
      (libsource (lib "eagle-import") (part "R-EU_R0805"))
    )
    (comp (ref "R26")
      (value "100")
      (footprint "eagle-import:R0805")
      (libsource (lib "eagle-import") (part "R-EU_R0805"))
    )
    (comp (ref "U4")
      (value "LM5022MSOP-10")
      (footprint "eagle-import:MSOP-10-NOPAD")
      (libsource (lib "eagle-import") (part "LM5022MSOP-10"))
    )
    (comp (ref "D20")
      (value "1N4148")
      (footprint "eagle-import:SOD323-W")
      (libsource (lib "eagle-import") (part "DIODE-SOD323-W"))
    )
    (comp (ref "D21")
      (value "1N4148")
      (footprint "eagle-import:SOD323-W")
      (libsource (lib "eagle-import") (part "DIODE-SOD323-W"))
    )
    (comp (ref "D22")
      (value "1N4148")
      (footprint "eagle-import:SOD323-W")
      (libsource (lib "eagle-import") (part "DIODE-SOD323-W"))
    )
    (comp (ref "PAD9")
      (value "WIREPAD1,6/0,8")
      (footprint "eagle-import:1,6_0,8")
      (libsource (lib "eagle-import") (part "WIREPAD1,6/0,8"))
    )
    (comp (ref "PAD10")
      (value "WIREPAD1,6/0,8")
      (footprint "eagle-import:1,6_0,8")
      (libsource (lib "eagle-import") (part "WIREPAD1,6/0,8"))
    )
    (comp (ref "PAD11")
      (value "WIREPAD1,6/0,8")
      (footprint "eagle-import:1,6_0,8")
      (libsource (lib "eagle-import") (part "WIREPAD1,6/0,8"))
    )
    (comp (ref "PAD12")
      (value "WIREPAD1,6/0,8")
      (footprint "eagle-import:1,6_0,8")
      (libsource (lib "eagle-import") (part "WIREPAD1,6/0,8"))
    )
    (comp (ref "R63")
      (value "R-EU_R0805")
      (footprint "eagle-import:R0805")
      (libsource (lib "eagle-import") (part "R-EU_R0805"))
    )
    (comp (ref "R64")
      (value "R-EU_R0805")
      (footprint "eagle-import:R0805")
      (libsource (lib "eagle-import") (part "R-EU_R0805"))
    )
    (comp (ref "R65")
      (value "R-EU_R0805")
      (footprint "eagle-import:R0805")
      (libsource (lib "eagle-import") (part "R-EU_R0805"))
    )
    (comp (ref "T9")
      (value "BSP78")
      (footprint "eagle-import:SOT223")
      (libsource (lib "eagle-import") (part "NMOSSOT223"))
    )
    (comp (ref "T10")
      (value "BSP78")
      (footprint "eagle-import:SOT223")
      (libsource (lib "eagle-import") (part "NMOSSOT223"))
    )
    (comp (ref "T11")
      (value "BSP78")
      (footprint "eagle-import:SOT223")
      (libsource (lib "eagle-import") (part "NMOSSOT223"))
    )
    (comp (ref "X2")
      (value "F09D")
      (footprint "eagle-import:F09D")
      (libsource (lib "eagle-import") (part "F09D"))
    )
    (comp (ref "C19")
      (value "2nF")
      (footprint "eagle-import:C1206K")
      (libsource (lib "eagle-import") (part "C-EUC1206K"))
    )
    (comp (ref "D5")
      (value "GF1")
      (footprint "eagle-import:SMA-DO214AC")
      (libsource (lib "eagle-import") (part "GF1"))
    )
    (comp (ref "IC2")
      (value "NE555D")
      (footprint "eagle-import:SO08")
      (libsource (lib "eagle-import") (part "555DNE"))
    )
    (comp (ref "R27")
      (value "30k")
      (footprint "eagle-import:R0805")
      (libsource (lib "eagle-import") (part "R-EU_R0805"))
    )
    (comp (ref "R28")
      (value "100k")
      (footprint "eagle-import:R0805")
      (libsource (lib "eagle-import") (part "R-EU_R0805"))
    )
    (comp (ref "R29")
      (value "10k")
      (footprint "eagle-import:R0805")
      (libsource (lib "eagle-import") (part "R-EU_R0805"))
    )
    (comp (ref "0")
      (value "SMD2")
      (footprint "eagle-import:SMD1,27-2,54")
      (libsource (lib "eagle-import") (part "SMD2"))
    )
    (comp (ref "1")
      (value "SMD2")
      (footprint "eagle-import:SMD1,27-2,54")
      (libsource (lib "eagle-import") (part "SMD2"))
    )
    (comp (ref "2")
      (value "SMD2")
      (footprint "eagle-import:SMD1,27-2,54")
      (libsource (lib "eagle-import") (part "SMD2"))
    )
    (comp (ref "3")
      (value "SMD2")
      (footprint "eagle-import:SMD1,27-2,54")
      (libsource (lib "eagle-import") (part "SMD2"))
    )
    (comp (ref "4")
      (value "SMD2")
      (footprint "eagle-import:SMD1,27-2,54")
      (libsource (lib "eagle-import") (part "SMD2"))
    )
    (comp (ref "5")
      (value "SMD2")
      (footprint "eagle-import:SMD1,27-2,54")
      (libsource (lib "eagle-import") (part "SMD2"))
    )
    (comp (ref "A")
      (value "SMD2")
      (footprint "eagle-import:SMD1,27-2,54")
      (libsource (lib "eagle-import") (part "SMD2"))
    )
    (comp (ref "LED1")
      (value "LED3MM")
      (footprint "eagle-import:LED3MM")
      (libsource (lib "eagle-import") (part "LED3MM"))
    )
    (comp (ref "LED2")
      (value "LED3MM")
      (footprint "eagle-import:LED3MM")
      (libsource (lib "eagle-import") (part "LED3MM"))
    )
    (comp (ref "LED3")
      (value "LED3MM")
      (footprint "eagle-import:LED3MM")
      (libsource (lib "eagle-import") (part "LED3MM"))
    )
    (comp (ref "LED4")
      (value "LED3MM")
      (footprint "eagle-import:LED3MM")
      (libsource (lib "eagle-import") (part "LED3MM"))
    )
    (comp (ref "LED5")
      (value "LED3MM")
      (footprint "eagle-import:LED3MM")
      (libsource (lib "eagle-import") (part "LED3MM"))
    )
    (comp (ref "LED6")
      (value "LED3MM")
      (footprint "eagle-import:LED3MM")
      (libsource (lib "eagle-import") (part "LED3MM"))
    )
    (comp (ref "LED7")
      (value "LED3MM")
      (footprint "eagle-import:LED3MM")
      (libsource (lib "eagle-import") (part "LED3MM"))
    )
    (comp (ref "LED8")
      (value "LED3MM")
      (footprint "eagle-import:LED3MM")
      (libsource (lib "eagle-import") (part "LED3MM"))
    )
    (comp (ref "N1")
      (value "IN-12A-IN-12")
      (footprint "eagle-import:IN-12")
      (libsource (lib "eagle-import") (part "IN-12A-IN-12"))
    )
    (comp (ref "R37")
      (value "10k")
      (footprint "eagle-import:R0805")
      (libsource (lib "eagle-import") (part "R-EU_R0805"))
    )
    (comp (ref "R38")
      (value "10k")
      (footprint "eagle-import:R0805")
      (libsource (lib "eagle-import") (part "R-EU_R0805"))
    )
    (comp (ref "R39")
      (value "10k")
      (footprint "eagle-import:R0805")
      (libsource (lib "eagle-import") (part "R-EU_R0805"))
    )
    (comp (ref "R40")
      (value "10k")
      (footprint "eagle-import:R0805")
      (libsource (lib "eagle-import") (part "R-EU_R0805"))
    )
    (comp (ref "T2")
      (value "MMBTA42LT1-NPN-SOT23-BEC")
      (footprint "eagle-import:SOT23-BEC")
      (fields (field (name "T") "SMBTA42"))
      (libsource (lib "eagle-import") (part "-NPN-SOT23-BECMMBTA42LT1"))
    )
    (comp (ref "T3")
      (value "MMBTA42LT1-NPN-SOT23-BEC")
      (footprint "eagle-import:SOT23-BEC")
      (fields (field (name "T") "SMBTA42"))
      (libsource (lib "eagle-import") (part "-NPN-SOT23-BECMMBTA42LT1"))
    )
    (comp (ref "U$3")
      (value "ZM1020")
      (footprint "eagle-import:ZM1020")
      (libsource (lib "eagle-import") (part "ZM1020"))
    )
  )
  (nets
    (net (code "1") (name "+12V") (class "Default")
      (node (ref "C12") (pin "1") (pinfunction "1_1") (pintype "passive"))
      (node (ref "C16") (pin "1") (pinfunction "1_1") (pintype "passive"))
      (node (ref "C27") (pin "1") (pinfunction "1_1") (pintype "passive"))
      (node (ref "C9") (pin "1") (pinfunction "1_1") (pintype "passive"))
      (node (ref "IC1") (pin "4") (pinfunction "R_4") (pintype "input"))
      (node (ref "IC1") (pin "8") (pinfunction "V+_8") (pintype "power_in"))
      (node (ref "IC2") (pin "4") (pinfunction "R_4") (pintype "input"))
      (node (ref "IC2") (pin "8") (pinfunction "V+_8") (pintype "power_in"))
      (node (ref "IC3") (pin "4") (pinfunction "R_4") (pintype "input"))
      (node (ref "IC3") (pin "8") (pinfunction "V+_8") (pintype "power_in"))
      (node (ref "IC4") (pin "4") (pinfunction "R_4") (pintype "input"))
      (node (ref "IC4") (pin "8") (pinfunction "V+_8") (pintype "power_in"))
      (node (ref "IC5") (pin "4") (pinfunction "R_4") (pintype "input"))
      (node (ref "IC5") (pin "8") (pinfunction "V+_8") (pintype "power_in"))
      (node (ref "IC6") (pin "4") (pinfunction "R_4") (pintype "input"))
      (node (ref "IC6") (pin "8") (pinfunction "V+_8") (pintype "power_in"))
      (node (ref "IC7") (pin "4") (pinfunction "R_4") (pintype "input"))
      (node (ref "IC7") (pin "8") (pinfunction "V+_8") (pintype "power_in"))
      (node (ref "L1") (pin "1") (pinfunction "1_1") (pintype "passive"))
      (node (ref "L3") (pin "1") (pinfunction "1_1") (pintype "passive"))
      (node (ref "L5") (pin "1") (pinfunction "1_1") (pintype "passive"))
      (node (ref "L7") (pin "1") (pinfunction "1_1") (pintype "passive"))
      (node (ref "R14") (pin "1") (pinfunction "1_1") (pintype "passive"))
      (node (ref "R23") (pin "1") (pinfunction "1_1") (pintype "passive"))
      (node (ref "R38") (pin "1") (pinfunction "1_1") (pintype "passive"))
      (node (ref "R40") (pin "1") (pinfunction "1_1") (pintype "passive"))
      (node (ref "R51") (pin "1") (pinfunction "1_1") (pintype "passive"))
      (node (ref "U1") (pin "10") (pinfunction "VIN_10") (pintype "bidirectional"))
      (node (ref "U2") (pin "10") (pinfunction "VIN_10") (pintype "bidirectional"))
      (node (ref "U3") (pin "8") (pinfunction "VIN_8") (pintype "power_in"))
      (node (ref "U4") (pin "1") (pinfunction "VIN_1") (pintype "bidirectional"))
    )
    (net (code "2") (name "CTS") (class "Default")
      (node (ref "R57") (pin "1") (pinfunction "1_1") (pintype "passive"))
      (node (ref "R60") (pin "1") (pinfunction "1_1") (pintype "passive"))
      (node (ref "R63") (pin "1") (pinfunction "1_1") (pintype "passive"))
      (node (ref "R66") (pin "1") (pinfunction "1_1") (pintype "passive"))
      (node (ref "X1") (pin "8") (pinfunction "8_8") (pintype "passive"))
      (node (ref "X2") (pin "8") (pinfunction "8_8") (pintype "passive"))
      (node (ref "X3") (pin "8") (pinfunction "8_8") (pintype "passive"))
      (node (ref "X4") (pin "8") (pinfunction "8_8") (pintype "passive"))
    )
    (net (code "3") (name "DCD") (class "Default")
      (node (ref "R59") (pin "1") (pinfunction "1_1") (pintype "passive"))
      (node (ref "R62") (pin "1") (pinfunction "1_1") (pintype "passive"))
      (node (ref "R65") (pin "1") (pinfunction "1_1") (pintype "passive"))
      (node (ref "R68") (pin "1") (pinfunction "1_1") (pintype "passive"))
      (node (ref "X1") (pin "1") (pinfunction "1_1") (pintype "passive"))
      (node (ref "X2") (pin "1") (pinfunction "1_1") (pintype "passive"))
      (node (ref "X3") (pin "1") (pinfunction "1_1") (pintype "passive"))
      (node (ref "X4") (pin "1") (pinfunction "1_1") (pintype "passive"))
    )
    (net (code "4") (name "DSR") (class "Default")
      (node (ref "R58") (pin "1") (pinfunction "1_1") (pintype "passive"))
      (node (ref "R61") (pin "1") (pinfunction "1_1") (pintype "passive"))
      (node (ref "R64") (pin "1") (pinfunction "1_1") (pintype "passive"))
      (node (ref "R67") (pin "1") (pinfunction "1_1") (pintype "passive"))
      (node (ref "X1") (pin "6") (pinfunction "6_6") (pintype "passive"))
      (node (ref "X2") (pin "6") (pinfunction "6_6") (pintype "passive"))
      (node (ref "X3") (pin "6") (pinfunction "6_6") (pintype "passive"))
      (node (ref "X4") (pin "6") (pinfunction "6_6") (pintype "passive"))
    )
    (net (code "5") (name "DTR") (class "Default")
      (node (ref "D16") (pin "A") (pinfunction "A_A") (pintype "passive"))
      (node (ref "D19") (pin "A") (pinfunction "A_A") (pintype "passive"))
      (node (ref "D22") (pin "A") (pinfunction "A_A") (pintype "passive"))
      (node (ref "D26") (pin "A") (pinfunction "A_A") (pintype "passive"))
      (node (ref "X1") (pin "4") (pinfunction "4_4") (pintype "passive"))
      (node (ref "X2") (pin "4") (pinfunction "4_4") (pintype "passive"))
      (node (ref "X3") (pin "4") (pinfunction "4_4") (pintype "passive"))
      (node (ref "X4") (pin "4") (pinfunction "4_4") (pintype "passive"))
    )
    (net (code "6") (name "GND") (class "Default")
      (node (ref "C1") (pin "2") (pinfunction "2_2") (pintype "passive"))
      (node (ref "C10") (pin "2") (pinfunction "2_2") (pintype "passive"))
      (node (ref "C12") (pin "2") (pinfunction "2_2") (pintype "passive"))
      (node (ref "C13") (pin "2") (pinfunction "2_2") (pintype "passive"))
      (node (ref "C14") (pin "2") (pinfunction "2_2") (pintype "passive"))
      (node (ref "C15") (pin "2") (pinfunction "2_2") (pintype "passive"))
      (node (ref "C16") (pin "2") (pinfunction "2_2") (pintype "passive"))
      (node (ref "C17") (pin "2") (pinfunction "2_2") (pintype "passive"))
      (node (ref "C19") (pin "2") (pinfunction "2_2") (pintype "passive"))
      (node (ref "C2") (pin "2") (pinfunction "2_2") (pintype "passive"))
      (node (ref "C20") (pin "2") (pinfunction "2_2") (pintype "passive"))
      (node (ref "C21") (pin "2") (pinfunction "2_2") (pintype "passive"))
      (node (ref "C22") (pin "2") (pinfunction "2_2") (pintype "passive"))
      (node (ref "C23") (pin "2") (pinfunction "2_2") (pintype "passive"))
      (node (ref "C24") (pin "2") (pinfunction "2_2") (pintype "passive"))
      (node (ref "C25") (pin "2") (pinfunction "2_2") (pintype "passive"))
      (node (ref "C26") (pin "2") (pinfunction "2_2") (pintype "passive"))
      (node (ref "C27") (pin "2") (pinfunction "2_2") (pintype "passive"))
      (node (ref "C28") (pin "2") (pinfunction "2_2") (pintype "passive"))
      (node (ref "C3") (pin "2") (pinfunction "2_2") (pintype "passive"))
      (node (ref "C4") (pin "2") (pinfunction "2_2") (pintype "passive"))
      (node (ref "C5") (pin "2") (pinfunction "2_2") (pintype "passive"))
      (node (ref "C6") (pin "2") (pinfunction "2_2") (pintype "passive"))
      (node (ref "C7") (pin "2") (pinfunction "2_2") (pintype "passive"))
      (node (ref "C8") (pin "2") (pinfunction "2_2") (pintype "passive"))
      (node (ref "C9") (pin "2") (pinfunction "2_2") (pintype "passive"))
      (node (ref "D12") (pin "A") (pinfunction "A_A") (pintype "passive"))
      (node (ref "D13") (pin "A") (pinfunction "A_A") (pintype "passive"))
      (node (ref "IC1") (pin "1") (pinfunction "GND_1") (pintype "power_in"))
      (node (ref "IC2") (pin "1") (pinfunction "GND_1") (pintype "power_in"))
      (node (ref "IC3") (pin "1") (pinfunction "GND_1") (pintype "power_in"))
      (node (ref "IC4") (pin "1") (pinfunction "GND_1") (pintype "power_in"))
      (node (ref "IC5") (pin "1") (pinfunction "GND_1") (pintype "power_in"))
      (node (ref "IC6") (pin "1") (pinfunction "GND_1") (pintype "power_in"))
      (node (ref "IC7") (pin "1") (pinfunction "GND_1") (pintype "power_in"))
      (node (ref "LED1") (pin "K") (pinfunction "C_K") (pintype "passive"))
      (node (ref "LED18") (pin "C3") (pinfunction "C_C3") (pintype "passive"))
      (node (ref "LED20") (pin "C3") (pinfunction "C_C3") (pintype "passive"))
      (node (ref "LED22") (pin "C2") (pinfunction "C_C2") (pintype "passive"))
      (node (ref "LED22") (pin "C3") (pinfunction "C_C3") (pintype "passive"))
      (node (ref "LED5") (pin "K") (pinfunction "C_K") (pintype "passive"))
      (node (ref "PAD12") (pin "1") (pinfunction "P_1") (pintype "passive"))
      (node (ref "PAD16") (pin "1") (pinfunction "P_1") (pintype "passive"))
      (node (ref "PAD4") (pin "1") (pinfunction "P_1") (pintype "passive"))
      (node (ref "PAD8") (pin "1") (pinfunction "P_1") (pintype "passive"))
      (node (ref "R10") (pin "2") (pinfunction "2_2") (pintype "passive"))
      (node (ref "R11") (pin "2") (pinfunction "2_2") (pintype "passive"))
      (node (ref "R13") (pin "2") (pinfunction "2_2") (pintype "passive"))
      (node (ref "R16") (pin "2") (pinfunction "2_2") (pintype "passive"))
      (node (ref "R17") (pin "2") (pinfunction "2_2") (pintype "passive"))
      (node (ref "R20") (pin "2") (pinfunction "2_2") (pintype "passive"))
      (node (ref "R22") (pin "2") (pinfunction "2_2") (pintype "passive"))
      (node (ref "R28") (pin "2") (pinfunction "2_2") (pintype "passive"))
      (node (ref "R3") (pin "2") (pinfunction "2_2") (pintype "passive"))
      (node (ref "R31") (pin "2") (pinfunction "2_2") (pintype "passive"))
      (node (ref "R34") (pin "2") (pinfunction "2_2") (pintype "passive"))
      (node (ref "R41") (pin "2") (pinfunction "2_2") (pintype "passive"))
      (node (ref "R43") (pin "2") (pinfunction "2_2") (pintype "passive"))
      (node (ref "R46") (pin "2") (pinfunction "2_2") (pintype "passive"))
      (node (ref "R47") (pin "2") (pinfunction "2_2") (pintype "passive"))
      (node (ref "R48") (pin "2") (pinfunction "2_2") (pintype "passive"))
      (node (ref "R5") (pin "2") (pinfunction "2_2") (pintype "passive"))
      (node (ref "R50") (pin "2") (pinfunction "2_2") (pintype "passive"))
      (node (ref "R55") (pin "2") (pinfunction "2_2") (pintype "passive"))
      (node (ref "R6") (pin "2") (pinfunction "2_2") (pintype "passive"))
      (node (ref "R7") (pin "2") (pinfunction "2_2") (pintype "passive"))
      (node (ref "R9") (pin "2") (pinfunction "2_2") (pintype "passive"))
      (node (ref "T1") (pin "3") (pinfunction "S_3") (pintype "passive"))
      (node (ref "T10") (pin "3") (pinfunction "S_3") (pintype "passive"))
      (node (ref "T11") (pin "3") (pinfunction "S_3") (pintype "passive"))
      (node (ref "T12") (pin "3") (pinfunction "S_3") (pintype "passive"))
      (node (ref "T13") (pin "3") (pinfunction "S_3") (pintype "passive"))
      (node (ref "T14") (pin "3") (pinfunction "S_3") (pintype "passive"))
      (node (ref "T2") (pin "E") (pinfunction "E_E") (pintype "passive"))
      (node (ref "T3") (pin "E") (pinfunction "E_E") (pintype "passive"))
      (node (ref "T4") (pin "3") (pinfunction "S_3") (pintype "passive"))
      (node (ref "T5") (pin "3") (pinfunction "S_3") (pintype "passive"))
      (node (ref "T6") (pin "3") (pinfunction "S_3") (pintype "passive"))
      (node (ref "T7") (pin "3") (pinfunction "S_3") (pintype "passive"))
      (node (ref "T8") (pin "3") (pinfunction "S_3") (pintype "passive"))
      (node (ref "T9") (pin "3") (pinfunction "S_3") (pintype "passive"))
      (node (ref "U$12") (pin "C") (pinfunction "C_C") (pintype "bidirectional"))
      (node (ref "U$13") (pin "C") (pinfunction "C_C") (pintype "bidirectional"))
      (node (ref "U$8") (pin "C") (pinfunction "C_C") (pintype "bidirectional"))
      (node (ref "U$9") (pin "C") (pinfunction "C_C") (pintype "bidirectional"))
      (node (ref "U1") (pin "5") (pinfunction "SYNC_5") (pintype "bidirectional"))
      (node (ref "U1") (pin "PAD") (pinfunction "PAD_PAD") (pintype "bidirectional"))
      (node (ref "U2") (pin "5") (pinfunction "SYNC_5") (pintype "bidirectional"))
      (node (ref "U2") (pin "PAD") (pinfunction "PAD_PAD") (pintype "bidirectional"))
      (node (ref "U3") (pin "4") (pinfunction "AGND_4") (pintype "power_in"))
      (node (ref "U3") (pin "5") (pinfunction "PGND_5") (pintype "power_in"))
      (node (ref "U4") (pin "6") (pinfunction "GND_6") (pintype "bidirectional"))
      (node (ref "X1") (pin "5") (pinfunction "5_5") (pintype "passive"))
      (node (ref "X2") (pin "5") (pinfunction "5_5") (pintype "passive"))
      (node (ref "X3") (pin "5") (pinfunction "5_5") (pintype "passive"))
      (node (ref "X4") (pin "5") (pinfunction "5_5") (pintype "passive"))
    )
    (net (code "7") (name "Net-(0-P)") (class "Default")
      (node (ref "0") (pin "1") (pinfunction "P_1") (pintype "passive"))
      (node (ref "N1") (pin "0") (pinfunction "0_0") (pintype "bidirectional"))
    )
    (net (code "8") (name "Net-(1-P)") (class "Default")
      (node (ref "1") (pin "1") (pinfunction "P_1") (pintype "passive"))
      (node (ref "N1") (pin "1") (pinfunction "1_1") (pintype "bidirectional"))
    )
    (net (code "9") (name "Net-(2-P)") (class "Default")
      (node (ref "2") (pin "1") (pinfunction "P_1") (pintype "passive"))
      (node (ref "N1") (pin "2") (pinfunction "2_2") (pintype "bidirectional"))
    )
    (net (code "10") (name "Net-(3-P)") (class "Default")
      (node (ref "3") (pin "1") (pinfunction "P_1") (pintype "passive"))
      (node (ref "N1") (pin "3") (pinfunction "3_3") (pintype "bidirectional"))
    )
    (net (code "11") (name "Net-(4-P)") (class "Default")
      (node (ref "4") (pin "1") (pinfunction "P_1") (pintype "passive"))
      (node (ref "N1") (pin "4") (pinfunction "4_4") (pintype "bidirectional"))
    )
    (net (code "12") (name "Net-(5-P)") (class "Default")
      (node (ref "5") (pin "1") (pinfunction "P_1") (pintype "passive"))
      (node (ref "N1") (pin "5") (pinfunction "5_5") (pintype "bidirectional"))
    )
    (net (code "13") (name "Net-(12-P)") (class "Default")
      (node (ref "12") (pin "1") (pinfunction "P_1") (pintype "passive"))
      (node (ref "R71") (pin "1") (pinfunction "1_1") (pintype "passive"))
      (node (ref "R72") (pin "1") (pinfunction "1_1") (pintype "passive"))
    )
    (net (code "14") (name "Net-(13-P)") (class "Default")
      (node (ref "13") (pin "1") (pinfunction "P_1") (pintype "passive"))
      (node (ref "R73") (pin "1") (pinfunction "1_1") (pintype "passive"))
      (node (ref "R74") (pin "1") (pinfunction "1_1") (pintype "passive"))
    )
    (net (code "15") (name "Net-(14-P)") (class "Default")
      (node (ref "14") (pin "1") (pinfunction "P_1") (pintype "passive"))
      (node (ref "R75") (pin "1") (pinfunction "1_1") (pintype "passive"))
      (node (ref "R76") (pin "1") (pinfunction "1_1") (pintype "passive"))
    )
    (net (code "16") (name "Net-(15-P)") (class "Default")
      (node (ref "15") (pin "1") (pinfunction "P_1") (pintype "passive"))
      (node (ref "N3") (pin "0") (pinfunction "0_0") (pintype "bidirectional"))
    )
    (net (code "17") (name "Net-(16-P)") (class "Default")
      (node (ref "16") (pin "1") (pinfunction "P_1") (pintype "passive"))
      (node (ref "N3") (pin "1") (pinfunction "1_1") (pintype "bidirectional"))
    )
    (net (code "18") (name "Net-(17-P)") (class "Default")
      (node (ref "17") (pin "1") (pinfunction "P_1") (pintype "passive"))
      (node (ref "N3") (pin "2") (pinfunction "2_2") (pintype "bidirectional"))
    )
    (net (code "19") (name "Net-(18-P)") (class "Default")
      (node (ref "18") (pin "1") (pinfunction "P_1") (pintype "passive"))
      (node (ref "N3") (pin "3") (pinfunction "3_3") (pintype "bidirectional"))
    )
    (net (code "20") (name "Net-(19-P)") (class "Default")
      (node (ref "19") (pin "1") (pinfunction "P_1") (pintype "passive"))
      (node (ref "N3") (pin "4") (pinfunction "4_4") (pintype "bidirectional"))
    )
    (net (code "21") (name "Net-(20-P)") (class "Default")
      (node (ref "20") (pin "1") (pinfunction "P_1") (pintype "passive"))
      (node (ref "N3") (pin "5") (pinfunction "5_5") (pintype "bidirectional"))
    )
    (net (code "22") (name "Net-(21-P)") (class "Default")
      (node (ref "21") (pin "1") (pinfunction "P_1") (pintype "passive"))
      (node (ref "R77") (pin "1") (pinfunction "1_1") (pintype "passive"))
      (node (ref "R78") (pin "1") (pinfunction "1_1") (pintype "passive"))
    )
    (net (code "23") (name "Net-(A-P)") (class "Default")
      (node (ref "A") (pin "1") (pinfunction "P_1") (pintype "passive"))
      (node (ref "N1") (pin "A") (pinfunction "A_A") (pintype "bidirectional"))
    )
    (net (code "24") (name "Net-(A2-P)") (class "Default")
      (node (ref "A2") (pin "1") (pinfunction "P_1") (pintype "passive"))
      (node (ref "N3") (pin "A") (pinfunction "A_A") (pintype "bidirectional"))
    )
    (net (code "25") (name "Net-(C3-Pad1)") (class "Default")
      (node (ref "C3") (pin "1") (pinfunction "1_1") (pintype "passive"))
      (node (ref "R18") (pin "2") (pinfunction "2_2") (pintype "passive"))
    )
    (net (code "26") (name "Net-(C4-Pad1)") (class "Default")
      (node (ref "C4") (pin "1") (pinfunction "1_1") (pintype "passive"))
      (node (ref "R15") (pin "2") (pinfunction "2_2") (pintype "passive"))
    )
    (net (code "27") (name "Net-(C7-Pad1)") (class "Default")
      (node (ref "C7") (pin "1") (pinfunction "1_1") (pintype "passive"))
      (node (ref "D2") (pin "C") (pinfunction "C_C") (pintype "passive"))
      (node (ref "R1") (pin "2") (pinfunction "2_2") (pintype "passive"))
    )
    (net (code "28") (name "Net-(C10-Pad1)") (class "Default")
      (node (ref "C10") (pin "1") (pinfunction "1_1") (pintype "passive"))
      (node (ref "D3") (pin "C") (pinfunction "C_C") (pintype "passive"))
      (node (ref "R19") (pin "2") (pinfunction "2_2") (pintype "passive"))
    )
    (net (code "29") (name "Net-(C11-Pad1)") (class "Default")
      (node (ref "C11") (pin "1") (pinfunction "1_1") (pintype "passive"))
      (node (ref "R24") (pin "2") (pinfunction "2_2") (pintype "passive"))
    )
    (net (code "30") (name "Net-(C14-Pad1)") (class "Default")
      (node (ref "C14") (pin "1") (pinfunction "1_1") (pintype "passive"))
      (node (ref "D4") (pin "C") (pinfunction "C_C") (pintype "passive"))
      (node (ref "R25") (pin "2") (pinfunction "2_2") (pintype "passive"))
    )
    (net (code "31") (name "Net-(C23-Pad1)") (class "Default")
      (node (ref "C23") (pin "1") (pinfunction "1_1") (pintype "passive"))
      (node (ref "R52") (pin "2") (pinfunction "2_2") (pintype "passive"))
    )
    (net (code "32") (name "Net-(C25-Pad1)") (class "Default")
      (node (ref "C25") (pin "1") (pinfunction "1_1") (pintype "passive"))
      (node (ref "D10") (pin "C") (pinfunction "C_C") (pintype "passive"))
      (node (ref "R53") (pin "2") (pinfunction "2_2") (pintype "passive"))
    )
    (net (code "33") (name "Net-(D1-C)") (class "Default")
      (node (ref "C2") (pin "1") (pinfunction "1_1") (pintype "passive"))
      (node (ref "D1") (pin "K") (pinfunction "C_K") (pintype "passive"))
      (node (ref "D13") (pin "C") (pinfunction "C_C") (pintype "passive"))
      (node (ref "IC1") (pin "2") (pinfunction "TR_2") (pintype "input"))
      (node (ref "IC1") (pin "6") (pinfunction "THR_6") (pintype "input"))
      (node (ref "R3") (pin "1") (pinfunction "1_1") (pintype "passive"))
    )
    (net (code "34") (name "Net-(D1-PadA)") (class "Default")
      (node (ref "D1") (pin "A") (pinfunction "A_A") (pintype "passive"))
      (node (ref "R2") (pin "1") (pinfunction "1_1") (pintype "passive"))
    )
    (net (code "35") (name "Net-(D5-C)") (class "Default")
      (node (ref "C19") (pin "1") (pinfunction "1_1") (pintype "passive"))
      (node (ref "D5") (pin "K") (pinfunction "C_K") (pintype "passive"))
      (node (ref "IC2") (pin "2") (pinfunction "TR_2") (pintype "input"))
      (node (ref "IC2") (pin "6") (pinfunction "THR_6") (pintype "input"))
      (node (ref "R28") (pin "1") (pinfunction "1_1") (pintype "passive"))
    )
    (net (code "36") (name "Net-(D5-PadA)") (class "Default")
      (node (ref "D5") (pin "A") (pinfunction "A_A") (pintype "passive"))
      (node (ref "R27") (pin "1") (pinfunction "1_1") (pintype "passive"))
    )
    (net (code "37") (name "Net-(D6-C)") (class "Default")
      (node (ref "C20") (pin "1") (pinfunction "1_1") (pintype "passive"))
      (node (ref "D6") (pin "K") (pinfunction "C_K") (pintype "passive"))
      (node (ref "IC3") (pin "2") (pinfunction "TR_2") (pintype "input"))
      (node (ref "IC3") (pin "6") (pinfunction "THR_6") (pintype "input"))
      (node (ref "R31") (pin "1") (pinfunction "1_1") (pintype "passive"))
    )
    (net (code "38") (name "Net-(D6-PadA)") (class "Default")
      (node (ref "D6") (pin "A") (pinfunction "A_A") (pintype "passive"))
      (node (ref "R30") (pin "1") (pinfunction "1_1") (pintype "passive"))
    )
    (net (code "39") (name "Net-(D7-C)") (class "Default")
      (node (ref "C21") (pin "1") (pinfunction "1_1") (pintype "passive"))
      (node (ref "D7") (pin "K") (pinfunction "C_K") (pintype "passive"))
      (node (ref "IC4") (pin "2") (pinfunction "TR_2") (pintype "input"))
      (node (ref "IC4") (pin "6") (pinfunction "THR_6") (pintype "input"))
      (node (ref "R34") (pin "1") (pinfunction "1_1") (pintype "passive"))
    )
    (net (code "40") (name "Net-(D7-PadA)") (class "Default")
      (node (ref "D7") (pin "A") (pinfunction "A_A") (pintype "passive"))
      (node (ref "R33") (pin "1") (pinfunction "1_1") (pintype "passive"))
    )
    (net (code "41") (name "Net-(D8-C)") (class "Default")
      (node (ref "C1") (pin "1") (pinfunction "1_1") (pintype "passive"))
      (node (ref "D12") (pin "C") (pinfunction "C_C") (pintype "passive"))
      (node (ref "D8") (pin "K") (pinfunction "C_K") (pintype "passive"))
      (node (ref "IC6") (pin "2") (pinfunction "TR_2") (pintype "input"))
      (node (ref "IC6") (pin "6") (pinfunction "THR_6") (pintype "input"))
      (node (ref "R43") (pin "1") (pinfunction "1_1") (pintype "passive"))
    )
    (net (code "42") (name "Net-(D8-PadA)") (class "Default")
      (node (ref "D8") (pin "A") (pinfunction "A_A") (pintype "passive"))
      (node (ref "R42") (pin "1") (pinfunction "1_1") (pintype "passive"))
    )
    (net (code "43") (name "Net-(D9-C)") (class "Default")
      (node (ref "C22") (pin "1") (pinfunction "1_1") (pintype "passive"))
      (node (ref "D9") (pin "K") (pinfunction "C_K") (pintype "passive"))
      (node (ref "IC5") (pin "2") (pinfunction "TR_2") (pintype "input"))
      (node (ref "IC5") (pin "6") (pinfunction "THR_6") (pintype "input"))
      (node (ref "R41") (pin "1") (pinfunction "1_1") (pintype "passive"))
    )
    (net (code "44") (name "Net-(D9-PadA)") (class "Default")
      (node (ref "D9") (pin "A") (pinfunction "A_A") (pintype "passive"))
      (node (ref "R36") (pin "1") (pinfunction "1_1") (pintype "passive"))
    )
    (net (code "45") (name "Net-(D11-C)") (class "Default")
      (node (ref "C28") (pin "1") (pinfunction "1_1") (pintype "passive"))
      (node (ref "D11") (pin "K") (pinfunction "C_K") (pintype "passive"))
      (node (ref "IC7") (pin "2") (pinfunction "TR_2") (pintype "input"))
      (node (ref "IC7") (pin "6") (pinfunction "THR_6") (pintype "input"))
      (node (ref "R55") (pin "1") (pinfunction "1_1") (pintype "passive"))
    )
    (net (code "46") (name "Net-(D11-PadA)") (class "Default")
      (node (ref "D11") (pin "A") (pinfunction "A_A") (pintype "passive"))
      (node (ref "R54") (pin "1") (pinfunction "1_1") (pintype "passive"))
    )
    (net (code "47") (name "Net-(D14-PadA)") (class "Default")
      (node (ref "D14") (pin "A") (pinfunction "A_A") (pintype "passive"))
      (node (ref "X3") (pin "7") (pinfunction "7_7") (pintype "passive"))
    )
    (net (code "48") (name "Net-(D17-PadA)") (class "Default")
      (node (ref "D17") (pin "A") (pinfunction "A_A") (pintype "passive"))
      (node (ref "X1") (pin "7") (pinfunction "7_7") (pintype "passive"))
    )
    (net (code "49") (name "Net-(D20-PadA)") (class "Default")
      (node (ref "D20") (pin "A") (pinfunction "A_A") (pintype "passive"))
      (node (ref "X2") (pin "7") (pinfunction "7_7") (pintype "passive"))
    )
    (net (code "50") (name "Net-(D24-PadA)") (class "Default")
      (node (ref "D24") (pin "A") (pinfunction "A_A") (pintype "passive"))
      (node (ref "X4") (pin "7") (pinfunction "7_7") (pintype "passive"))
    )
    (net (code "51") (name "Net-(IC1-CV)") (class "Default")
      (node (ref "IC1") (pin "5") (pinfunction "CV_5") (pintype "input"))
      (node (ref "R4") (pin "1") (pinfunction "1_1") (pintype "passive"))
    )
    (net (code "52") (name "Net-(IC1-Q)") (class "Default")
      (node (ref "IC1") (pin "3") (pinfunction "Q_3") (pintype "output"))
      (node (ref "R4") (pin "2") (pinfunction "2_2") (pintype "passive"))
    )
    (net (code "53") (name "Net-(IC2-CV)") (class "Default")
      (node (ref "IC2") (pin "5") (pinfunction "CV_5") (pintype "input"))
      (node (ref "R29") (pin "1") (pinfunction "1_1") (pintype "passive"))
    )
    (net (code "54") (name "Net-(IC2-Q)") (class "Default")
      (node (ref "IC2") (pin "3") (pinfunction "Q_3") (pintype "output"))
      (node (ref "R29") (pin "2") (pinfunction "2_2") (pintype "passive"))
    )
    (net (code "55") (name "Net-(IC3-CV)") (class "Default")
      (node (ref "IC3") (pin "5") (pinfunction "CV_5") (pintype "input"))
      (node (ref "R32") (pin "1") (pinfunction "1_1") (pintype "passive"))
    )
    (net (code "56") (name "Net-(IC3-Q)") (class "Default")
      (node (ref "IC3") (pin "3") (pinfunction "Q_3") (pintype "output"))
      (node (ref "R32") (pin "2") (pinfunction "2_2") (pintype "passive"))
    )
    (net (code "57") (name "Net-(IC4-CV)") (class "Default")
      (node (ref "IC4") (pin "5") (pinfunction "CV_5") (pintype "input"))
      (node (ref "R35") (pin "1") (pinfunction "1_1") (pintype "passive"))
    )
    (net (code "58") (name "Net-(IC4-Q)") (class "Default")
      (node (ref "IC4") (pin "3") (pinfunction "Q_3") (pintype "output"))
      (node (ref "R35") (pin "2") (pinfunction "2_2") (pintype "passive"))
    )
    (net (code "59") (name "Net-(IC5-CV)") (class "Default")
      (node (ref "IC5") (pin "5") (pinfunction "CV_5") (pintype "input"))
      (node (ref "R45") (pin "1") (pinfunction "1_1") (pintype "passive"))
    )
    (net (code "60") (name "Net-(IC5-Q)") (class "Default")
      (node (ref "IC5") (pin "3") (pinfunction "Q_3") (pintype "output"))
      (node (ref "R45") (pin "2") (pinfunction "2_2") (pintype "passive"))
    )
    (net (code "61") (name "Net-(IC6-CV)") (class "Default")
      (node (ref "IC6") (pin "5") (pinfunction "CV_5") (pintype "input"))
      (node (ref "R44") (pin "1") (pinfunction "1_1") (pintype "passive"))
    )
    (net (code "62") (name "Net-(IC6-Q)") (class "Default")
      (node (ref "IC6") (pin "3") (pinfunction "Q_3") (pintype "output"))
      (node (ref "R44") (pin "2") (pinfunction "2_2") (pintype "passive"))
    )
    (net (code "63") (name "Net-(IC7-CV)") (class "Default")
      (node (ref "IC7") (pin "5") (pinfunction "CV_5") (pintype "input"))
      (node (ref "R56") (pin "1") (pinfunction "1_1") (pintype "passive"))
    )
    (net (code "64") (name "Net-(IC7-Q)") (class "Default")
      (node (ref "IC7") (pin "3") (pinfunction "Q_3") (pintype "output"))
      (node (ref "R56") (pin "2") (pinfunction "2_2") (pintype "passive"))
    )
    (net (code "65") (name "Net-(LED2-C)") (class "Default")
      (node (ref "LED1") (pin "A") (pinfunction "A_A") (pintype "passive"))
      (node (ref "LED2") (pin "K") (pinfunction "C_K") (pintype "passive"))
    )
    (net (code "66") (name "Net-(LED2-PadA)") (class "Default")
      (node (ref "LED2") (pin "A") (pinfunction "A_A") (pintype "passive"))
      (node (ref "LED4") (pin "A") (pinfunction "A_A") (pintype "passive"))
      (node (ref "R38") (pin "2") (pinfunction "2_2") (pintype "passive"))
    )
    (net (code "67") (name "Net-(LED3-C)") (class "Default")
      (node (ref "LED3") (pin "K") (pinfunction "C_K") (pintype "passive"))
      (node (ref "T2") (pin "C") (pinfunction "C_C") (pintype "passive"))
    )
    (net (code "68") (name "Net-(LED4-C)") (class "Default")
      (node (ref "LED3") (pin "A") (pinfunction "A_A") (pintype "passive"))
      (node (ref "LED4") (pin "K") (pinfunction "C_K") (pintype "passive"))
    )
    (net (code "69") (name "Net-(LED6-C)") (class "Default")
      (node (ref "LED5") (pin "A") (pinfunction "A_A") (pintype "passive"))
      (node (ref "LED6") (pin "K") (pinfunction "C_K") (pintype "passive"))
    )
    (net (code "70") (name "Net-(LED6-PadA)") (class "Default")
      (node (ref "LED6") (pin "A") (pinfunction "A_A") (pintype "passive"))
      (node (ref "LED8") (pin "A") (pinfunction "A_A") (pintype "passive"))
      (node (ref "R40") (pin "2") (pinfunction "2_2") (pintype "passive"))
    )
    (net (code "71") (name "Net-(LED7-C)") (class "Default")
      (node (ref "LED7") (pin "K") (pinfunction "C_K") (pintype "passive"))
      (node (ref "T3") (pin "C") (pinfunction "C_C") (pintype "passive"))
    )
    (net (code "72") (name "Net-(LED8-C)") (class "Default")
      (node (ref "LED7") (pin "A") (pinfunction "A_A") (pintype "passive"))
      (node (ref "LED8") (pin "K") (pinfunction "C_K") (pintype "passive"))
    )
    (net (code "73") (name "Net-(LED17-A)") (class "Default")
      (node (ref "LED17") (pin "A3") (pinfunction "A_A3") (pintype "passive"))
      (node (ref "R73") (pin "2") (pinfunction "2_2") (pintype "passive"))
    )
    (net (code "74") (name "Net-(LED17-C)") (class "Default")
      (node (ref "LED17") (pin "C3") (pinfunction "C_C3") (pintype "passive"))
      (node (ref "LED18") (pin "A3") (pinfunction "A_A3") (pintype "passive"))
    )
    (net (code "75") (name "Net-(LED19-A)") (class "Default")
      (node (ref "LED19") (pin "A3") (pinfunction "A_A3") (pintype "passive"))
      (node (ref "R74") (pin "2") (pinfunction "2_2") (pintype "passive"))
    )
    (net (code "76") (name "Net-(LED19-C)") (class "Default")
      (node (ref "LED19") (pin "C3") (pinfunction "C_C3") (pintype "passive"))
      (node (ref "LED20") (pin "A3") (pinfunction "A_A3") (pintype "passive"))
    )
    (net (code "77") (name "Net-(LED21A-A)") (class "Default")
      (node (ref "LED21") (pin "A3") (pinfunction "A_A3") (pintype "passive"))
      (node (ref "R76") (pin "2") (pinfunction "2_2") (pintype "passive"))
    )
    (net (code "78") (name "Net-(LED21A-C)") (class "Default")
      (node (ref "LED21") (pin "C3") (pinfunction "C_C3") (pintype "passive"))
      (node (ref "LED22") (pin "A3") (pinfunction "A_A3") (pintype "passive"))
    )
    (net (code "79") (name "Net-(LED21B-A)") (class "Default")
      (node (ref "LED21") (pin "A2") (pinfunction "A_A2") (pintype "passive"))
      (node (ref "R75") (pin "2") (pinfunction "2_2") (pintype "passive"))
    )
    (net (code "80") (name "Net-(LED21B-C)") (class "Default")
      (node (ref "LED21") (pin "C2") (pinfunction "C_C2") (pintype "passive"))
      (node (ref "LED22") (pin "A2") (pinfunction "A_A2") (pintype "passive"))
    )
    (net (code "81") (name "Net-(PAD1-P)") (class "Default")
      (node (ref "PAD1") (pin "1") (pinfunction "P_1") (pintype "passive"))
      (node (ref "R57") (pin "2") (pinfunction "2_2") (pintype "passive"))
      (node (ref "T1") (pin "2") (pinfunction "D_2") (pintype "passive"))
    )
    (net (code "82") (name "Net-(PAD2-P)") (class "Default")
      (node (ref "PAD2") (pin "1") (pinfunction "P_1") (pintype "passive"))
      (node (ref "R58") (pin "2") (pinfunction "2_2") (pintype "passive"))
      (node (ref "T4") (pin "2") (pinfunction "D_2") (pintype "passive"))
    )
    (net (code "83") (name "Net-(PAD3-P)") (class "Default")
      (node (ref "PAD3") (pin "1") (pinfunction "P_1") (pintype "passive"))
      (node (ref "R59") (pin "2") (pinfunction "2_2") (pintype "passive"))
      (node (ref "T5") (pin "2") (pinfunction "D_2") (pintype "passive"))
    )
    (net (code "84") (name "Net-(PAD5-P)") (class "Default")
      (node (ref "PAD5") (pin "1") (pinfunction "P_1") (pintype "passive"))
      (node (ref "R60") (pin "2") (pinfunction "2_2") (pintype "passive"))
      (node (ref "T6") (pin "2") (pinfunction "D_2") (pintype "passive"))
    )
    (net (code "85") (name "Net-(PAD6-P)") (class "Default")
      (node (ref "PAD6") (pin "1") (pinfunction "P_1") (pintype "passive"))
      (node (ref "R61") (pin "2") (pinfunction "2_2") (pintype "passive"))
      (node (ref "T7") (pin "2") (pinfunction "D_2") (pintype "passive"))
    )
    (net (code "86") (name "Net-(PAD7-P)") (class "Default")
      (node (ref "PAD7") (pin "1") (pinfunction "P_1") (pintype "passive"))
      (node (ref "R62") (pin "2") (pinfunction "2_2") (pintype "passive"))
      (node (ref "T8") (pin "2") (pinfunction "D_2") (pintype "passive"))
    )
    (net (code "87") (name "Net-(PAD9-P)") (class "Default")
      (node (ref "PAD9") (pin "1") (pinfunction "P_1") (pintype "passive"))
      (node (ref "R63") (pin "2") (pinfunction "2_2") (pintype "passive"))
      (node (ref "T9") (pin "2") (pinfunction "D_2") (pintype "passive"))
    )
    (net (code "88") (name "Net-(PAD10-P)") (class "Default")
      (node (ref "PAD10") (pin "1") (pinfunction "P_1") (pintype "passive"))
      (node (ref "R64") (pin "2") (pinfunction "2_2") (pintype "passive"))
      (node (ref "T10") (pin "2") (pinfunction "D_2") (pintype "passive"))
    )
    (net (code "89") (name "Net-(PAD11-P)") (class "Default")
      (node (ref "PAD11") (pin "1") (pinfunction "P_1") (pintype "passive"))
      (node (ref "R65") (pin "2") (pinfunction "2_2") (pintype "passive"))
      (node (ref "T11") (pin "2") (pinfunction "D_2") (pintype "passive"))
    )
    (net (code "90") (name "Net-(PAD13-P)") (class "Default")
      (node (ref "PAD13") (pin "1") (pinfunction "P_1") (pintype "passive"))
      (node (ref "R66") (pin "2") (pinfunction "2_2") (pintype "passive"))
      (node (ref "T12") (pin "2") (pinfunction "D_2") (pintype "passive"))
    )
    (net (code "91") (name "Net-(PAD14-P)") (class "Default")
      (node (ref "PAD14") (pin "1") (pinfunction "P_1") (pintype "passive"))
      (node (ref "R67") (pin "2") (pinfunction "2_2") (pintype "passive"))
      (node (ref "T13") (pin "2") (pinfunction "D_2") (pintype "passive"))
    )
    (net (code "92") (name "Net-(PAD15-P)") (class "Default")
      (node (ref "PAD15") (pin "1") (pinfunction "P_1") (pintype "passive"))
      (node (ref "R68") (pin "2") (pinfunction "2_2") (pintype "passive"))
      (node (ref "T14") (pin "2") (pinfunction "D_2") (pintype "passive"))
    )
    (net (code "93") (name "Net-(Q1-D)") (class "Default")
      (node (ref "D2") (pin "A") (pinfunction "A_A") (pintype "passive"))
      (node (ref "L1") (pin "2") (pinfunction "2_2") (pintype "passive"))
      (node (ref "Q1") (pin "3") (pinfunction "D_3") (pintype "passive"))
    )
    (net (code "94") (name "Net-(Q1-G)") (class "Default")
      (node (ref "Q1") (pin "1") (pinfunction "G_1") (pintype "passive"))
      (node (ref "U2") (pin "7") (pinfunction "GATE_7") (pintype "bidirectional"))
    )
    (net (code "95") (name "Net-(Q1-S)") (class "Default")
      (node (ref "Q1") (pin "2") (pinfunction "S_2") (pintype "passive"))
      (node (ref "R9") (pin "1") (pinfunction "1_1") (pintype "passive"))
      (node (ref "U2") (pin "6") (pinfunction "SENSE_6") (pintype "bidirectional"))
    )
    (net (code "96") (name "Net-(Q2-D)") (class "Default")
      (node (ref "D3") (pin "A") (pinfunction "A_A") (pintype "passive"))
      (node (ref "L3") (pin "2") (pinfunction "2_2") (pintype "passive"))
      (node (ref "Q2") (pin "3") (pinfunction "D_3") (pintype "passive"))
    )
    (net (code "97") (name "Net-(Q2-G)") (class "Default")
      (node (ref "Q2") (pin "1") (pinfunction "G_1") (pintype "passive"))
      (node (ref "U3") (pin "6") (pinfunction "DR_6") (pintype "output"))
    )
    (net (code "98") (name "Net-(Q2-S)") (class "Default")
      (node (ref "C5") (pin "1") (pinfunction "1_1") (pintype "passive"))
      (node (ref "Q2") (pin "2") (pinfunction "S_2") (pintype "passive"))
      (node (ref "R5") (pin "1") (pinfunction "1_1") (pintype "passive"))
      (node (ref "U3") (pin "1") (pinfunction "ISEN_1") (pintype "input"))
    )
    (net (code "99") (name "Net-(Q3-D)") (class "Default")
      (node (ref "D4") (pin "A") (pinfunction "A_A") (pintype "passive"))
      (node (ref "L5") (pin "2") (pinfunction "2_2") (pintype "passive"))
      (node (ref "Q3") (pin "3") (pinfunction "D_3") (pintype "passive"))
    )
    (net (code "100") (name "Net-(Q3-G)") (class "Default")
      (node (ref "Q3") (pin "1") (pinfunction "G_1") (pintype "passive"))
      (node (ref "U4") (pin "5") (pinfunction "OUT_5") (pintype "bidirectional"))
    )
    (net (code "101") (name "Net-(Q3-S)") (class "Default")
      (node (ref "Q3") (pin "2") (pinfunction "S_2") (pintype "passive"))
      (node (ref "R16") (pin "1") (pinfunction "1_1") (pintype "passive"))
      (node (ref "R26") (pin "2") (pinfunction "2_2") (pintype "passive"))
    )
    (net (code "102") (name "Net-(Q4-D)") (class "Default")
      (node (ref "D10") (pin "A") (pinfunction "A_A") (pintype "passive"))
      (node (ref "L7") (pin "2") (pinfunction "2_2") (pintype "passive"))
      (node (ref "Q4") (pin "3") (pinfunction "D_3") (pintype "passive"))
    )
    (net (code "103") (name "Net-(Q4-G)") (class "Default")
      (node (ref "Q4") (pin "1") (pinfunction "G_1") (pintype "passive"))
      (node (ref "U1") (pin "7") (pinfunction "GATE_7") (pintype "bidirectional"))
    )
    (net (code "104") (name "Net-(Q4-S)") (class "Default")
      (node (ref "Q4") (pin "2") (pinfunction "S_2") (pintype "passive"))
      (node (ref "R46") (pin "1") (pinfunction "1_1") (pintype "passive"))
      (node (ref "U1") (pin "6") (pinfunction "SENSE_6") (pintype "bidirectional"))
    )
    (net (code "105") (name "Net-(R1-Pad1)") (class "Default")
      (node (ref "R1") (pin "1") (pinfunction "1_1") (pintype "passive"))
      (node (ref "R12") (pin "1") (pinfunction "1_1") (pintype "passive"))
    )
    (net (code "106") (name "Net-(R19-Pad1)") (class "Default")
      (node (ref "R19") (pin "1") (pinfunction "1_1") (pintype "passive"))
      (node (ref "R8") (pin "1") (pinfunction "1_1") (pintype "passive"))
    )
    (net (code "107") (name "Net-(R21-Pad1)") (class "Default")
      (node (ref "R21") (pin "1") (pinfunction "1_1") (pintype "passive"))
      (node (ref "R25") (pin "1") (pinfunction "1_1") (pintype "passive"))
    )
    (net (code "108") (name "Net-(R37-Pad1)") (class "Default")
      (node (ref "R37") (pin "1") (pinfunction "1_1") (pintype "passive"))
      (node (ref "T2") (pin "B") (pinfunction "B_B") (pintype "passive"))
    )
    (net (code "109") (name "Net-(R39-Pad1)") (class "Default")
      (node (ref "R39") (pin "1") (pinfunction "1_1") (pintype "passive"))
      (node (ref "T3") (pin "B") (pinfunction "B_B") (pintype "passive"))
    )
    (net (code "110") (name "Net-(R49-Pad1)") (class "Default")
      (node (ref "R49") (pin "1") (pinfunction "1_1") (pintype "passive"))
      (node (ref "R53") (pin "1") (pinfunction "1_1") (pintype "passive"))
    )
    (net (code "111") (name "Net-(R71-Pad2)") (class "Default")
      (node (ref "R71") (pin "2") (pinfunction "2_2") (pintype "passive"))
      (node (ref "U$5") (pin "A") (pinfunction "A_A") (pintype "bidirectional"))
    )
    (net (code "112") (name "Net-(R72-Pad2)") (class "Default")
      (node (ref "R72") (pin "2") (pinfunction "2_2") (pintype "passive"))
      (node (ref "U$6") (pin "A") (pinfunction "A_A") (pintype "bidirectional"))
    )
    (net (code "113") (name "Net-(R77-Pad2)") (class "Default")
      (node (ref "R77") (pin "2") (pinfunction "2_2") (pintype "passive"))
      (node (ref "U$12") (pin "A") (pinfunction "A_A") (pintype "bidirectional"))
    )
    (net (code "114") (name "Net-(R78-Pad2)") (class "Default")
      (node (ref "R78") (pin "2") (pinfunction "2_2") (pintype "passive"))
      (node (ref "U$13") (pin "A") (pinfunction "A_A") (pintype "bidirectional"))
    )
    (net (code "115") (name "Net-(T1-G)") (class "Default")
      (node (ref "D14") (pin "C") (pinfunction "C_C") (pintype "passive"))
      (node (ref "T1") (pin "1") (pinfunction "G_1") (pintype "passive"))
    )
    (net (code "116") (name "Net-(T4-G)") (class "Default")
      (node (ref "D15") (pin "C") (pinfunction "C_C") (pintype "passive"))
      (node (ref "T4") (pin "1") (pinfunction "G_1") (pintype "passive"))
    )
    (net (code "117") (name "Net-(T5-G)") (class "Default")
      (node (ref "D16") (pin "C") (pinfunction "C_C") (pintype "passive"))
      (node (ref "T5") (pin "1") (pinfunction "G_1") (pintype "passive"))
    )
    (net (code "118") (name "Net-(T6-G)") (class "Default")
      (node (ref "D17") (pin "C") (pinfunction "C_C") (pintype "passive"))
      (node (ref "T6") (pin "1") (pinfunction "G_1") (pintype "passive"))
    )
    (net (code "119") (name "Net-(T7-G)") (class "Default")
      (node (ref "D18") (pin "C") (pinfunction "C_C") (pintype "passive"))
      (node (ref "T7") (pin "1") (pinfunction "G_1") (pintype "passive"))
    )
    (net (code "120") (name "Net-(T8-G)") (class "Default")
      (node (ref "D19") (pin "C") (pinfunction "C_C") (pintype "passive"))
      (node (ref "T8") (pin "1") (pinfunction "G_1") (pintype "passive"))
    )
    (net (code "121") (name "Net-(T9-G)") (class "Default")
      (node (ref "D20") (pin "C") (pinfunction "C_C") (pintype "passive"))
      (node (ref "T9") (pin "1") (pinfunction "G_1") (pintype "passive"))
    )
    (net (code "122") (name "Net-(T10-G)") (class "Default")
      (node (ref "D21") (pin "C") (pinfunction "C_C") (pintype "passive"))
      (node (ref "T10") (pin "1") (pinfunction "G_1") (pintype "passive"))
    )
    (net (code "123") (name "Net-(T11-G)") (class "Default")
      (node (ref "D22") (pin "C") (pinfunction "C_C") (pintype "passive"))
      (node (ref "T11") (pin "1") (pinfunction "G_1") (pintype "passive"))
    )
    (net (code "124") (name "Net-(T12-G)") (class "Default")
      (node (ref "D24") (pin "C") (pinfunction "C_C") (pintype "passive"))
      (node (ref "T12") (pin "1") (pinfunction "G_1") (pintype "passive"))
    )
    (net (code "125") (name "Net-(T13-G)") (class "Default")
      (node (ref "D25") (pin "C") (pinfunction "C_C") (pintype "passive"))
      (node (ref "T13") (pin "1") (pinfunction "G_1") (pintype "passive"))
    )
    (net (code "126") (name "Net-(T14-G)") (class "Default")
      (node (ref "D26") (pin "C") (pinfunction "C_C") (pintype "passive"))
      (node (ref "T14") (pin "1") (pinfunction "G_1") (pintype "passive"))
    )
    (net (code "127") (name "Net-(U$5-PadC)") (class "Default")
      (node (ref "U$5") (pin "C") (pinfunction "C_C") (pintype "bidirectional"))
      (node (ref "U$8") (pin "A") (pinfunction "A_A") (pintype "bidirectional"))
    )
    (net (code "128") (name "Net-(U$6-PadC)") (class "Default")
      (node (ref "U$6") (pin "C") (pinfunction "C_C") (pintype "bidirectional"))
      (node (ref "U$9") (pin "A") (pinfunction "A_A") (pintype "bidirectional"))
    )
    (net (code "129") (name "Net-(U1-FBX)") (class "Default")
      (node (ref "R48") (pin "1") (pinfunction "1_1") (pintype "passive"))
      (node (ref "R49") (pin "2") (pinfunction "2_2") (pintype "passive"))
      (node (ref "U1") (pin "2") (pinfunction "FBX_2") (pintype "bidirectional"))
    )
    (net (code "130") (name "Net-(U1-INTVCC)") (class "Default")
      (node (ref "C26") (pin "1") (pinfunction "1_1") (pintype "passive"))
      (node (ref "U1") (pin "8") (pinfunction "INTVCC_8") (pintype "bidirectional"))
    )
    (net (code "131") (name "Net-(U1-RT)") (class "Default")
      (node (ref "R47") (pin "1") (pinfunction "1_1") (pintype "passive"))
      (node (ref "U1") (pin "4") (pinfunction "RT_4") (pintype "bidirectional"))
    )
    (net (code "132") (name "Net-(U1-SHDN)") (class "Default")
      (node (ref "R50") (pin "1") (pinfunction "1_1") (pintype "passive"))
      (node (ref "R51") (pin "2") (pinfunction "2_2") (pintype "passive"))
      (node (ref "U1") (pin "9") (pinfunction "SHDN_9") (pintype "bidirectional"))
    )
    (net (code "133") (name "Net-(U1-SS)") (class "Default")
      (node (ref "C24") (pin "1") (pinfunction "1_1") (pintype "passive"))
      (node (ref "U1") (pin "3") (pinfunction "SS_3") (pintype "bidirectional"))
    )
    (net (code "134") (name "Net-(U1-VC)") (class "Default")
      (node (ref "R52") (pin "1") (pinfunction "1_1") (pintype "passive"))
      (node (ref "U1") (pin "1") (pinfunction "VC_1") (pintype "bidirectional"))
    )
    (net (code "135") (name "Net-(U2-FBX)") (class "Default")
      (node (ref "R11") (pin "1") (pinfunction "1_1") (pintype "passive"))
      (node (ref "R12") (pin "2") (pinfunction "2_2") (pintype "passive"))
      (node (ref "U2") (pin "2") (pinfunction "FBX_2") (pintype "bidirectional"))
    )
    (net (code "136") (name "Net-(U2-INTVCC)") (class "Default")
      (node (ref "C8") (pin "1") (pinfunction "1_1") (pintype "passive"))
      (node (ref "U2") (pin "8") (pinfunction "INTVCC_8") (pintype "bidirectional"))
    )
    (net (code "137") (name "Net-(U2-RT)") (class "Default")
      (node (ref "R10") (pin "1") (pinfunction "1_1") (pintype "passive"))
      (node (ref "U2") (pin "4") (pinfunction "RT_4") (pintype "bidirectional"))
    )
    (net (code "138") (name "Net-(U2-SHDN)") (class "Default")
      (node (ref "R13") (pin "1") (pinfunction "1_1") (pintype "passive"))
      (node (ref "R14") (pin "2") (pinfunction "2_2") (pintype "passive"))
      (node (ref "U2") (pin "9") (pinfunction "SHDN_9") (pintype "bidirectional"))
    )
    (net (code "139") (name "Net-(U2-SS)") (class "Default")
      (node (ref "C6") (pin "1") (pinfunction "1_1") (pintype "passive"))
      (node (ref "U2") (pin "3") (pinfunction "SS_3") (pintype "bidirectional"))
    )
    (net (code "140") (name "Net-(U2-VC)") (class "Default")
      (node (ref "R15") (pin "1") (pinfunction "1_1") (pintype "passive"))
      (node (ref "U2") (pin "1") (pinfunction "VC_1") (pintype "bidirectional"))
    )
    (net (code "141") (name "Net-(U3-COMP)") (class "Default")
      (node (ref "R18") (pin "1") (pinfunction "1_1") (pintype "passive"))
      (node (ref "U3") (pin "2") (pinfunction "COMP_2") (pintype "input"))
    )
    (net (code "142") (name "Net-(U3-FA{slash}SD)") (class "Default")
      (node (ref "R6") (pin "1") (pinfunction "1_1") (pintype "passive"))
      (node (ref "U3") (pin "7") (pinfunction "FA/SD_7") (pintype "input"))
    )
    (net (code "143") (name "Net-(U3-FB)") (class "Default")
      (node (ref "R7") (pin "1") (pinfunction "1_1") (pintype "passive"))
      (node (ref "R8") (pin "2") (pinfunction "2_2") (pintype "passive"))
      (node (ref "U3") (pin "3") (pinfunction "FB_3") (pintype "input"))
    )
    (net (code "144") (name "Net-(U4-COMP)") (class "Default")
      (node (ref "C18") (pin "1") (pinfunction "1_1") (pintype "passive"))
      (node (ref "R24") (pin "1") (pinfunction "1_1") (pintype "passive"))
      (node (ref "U4") (pin "3") (pinfunction "COMP_3") (pintype "bidirectional"))
    )
    (net (code "145") (name "Net-(U4-CS)") (class "Default")
      (node (ref "C17") (pin "1") (pinfunction "1_1") (pintype "passive"))
      (node (ref "R26") (pin "1") (pinfunction "1_1") (pintype "passive"))
      (node (ref "U4") (pin "8") (pinfunction "CS_8") (pintype "bidirectional"))
    )
    (net (code "146") (name "Net-(U4-FB)") (class "Default")
      (node (ref "C11") (pin "2") (pinfunction "2_2") (pintype "passive"))
      (node (ref "C18") (pin "2") (pinfunction "2_2") (pintype "passive"))
      (node (ref "R20") (pin "1") (pinfunction "1_1") (pintype "passive"))
      (node (ref "R21") (pin "2") (pinfunction "2_2") (pintype "passive"))
      (node (ref "U4") (pin "2") (pinfunction "FB_2") (pintype "bidirectional"))
    )
    (net (code "147") (name "Net-(U4-RT)") (class "Default")
      (node (ref "R17") (pin "1") (pinfunction "1_1") (pintype "passive"))
      (node (ref "U4") (pin "9") (pinfunction "RT_9") (pintype "bidirectional"))
    )
    (net (code "148") (name "Net-(U4-SS)") (class "Default")
      (node (ref "C13") (pin "1") (pinfunction "1_1") (pintype "passive"))
      (node (ref "U4") (pin "10") (pinfunction "SS_10") (pintype "bidirectional"))
    )
    (net (code "149") (name "Net-(U4-UVLO)") (class "Default")
      (node (ref "R22") (pin "1") (pinfunction "1_1") (pintype "passive"))
      (node (ref "R23") (pin "2") (pinfunction "2_2") (pintype "passive"))
      (node (ref "U4") (pin "7") (pinfunction "UVLO_7") (pintype "bidirectional"))
    )
    (net (code "150") (name "Net-(U4-VCC)") (class "Default")
      (node (ref "C15") (pin "1") (pinfunction "1_1") (pintype "passive"))
      (node (ref "U4") (pin "4") (pinfunction "VCC_4") (pintype "bidirectional"))
    )
    (net (code "151") (name "RTS") (class "Default")
      (node (ref "D15") (pin "A") (pinfunction "A_A") (pintype "passive"))
      (node (ref "D18") (pin "A") (pinfunction "A_A") (pintype "passive"))
      (node (ref "D21") (pin "A") (pinfunction "A_A") (pintype "passive"))
      (node (ref "D25") (pin "A") (pinfunction "A_A") (pintype "passive"))
      (node (ref "X1") (pin "3") (pinfunction "3_3") (pintype "passive"))
      (node (ref "X2") (pin "3") (pinfunction "3_3") (pintype "passive"))
      (node (ref "X3") (pin "3") (pinfunction "3_3") (pintype "passive"))
      (node (ref "X4") (pin "3") (pinfunction "3_3") (pintype "passive"))
    )
    (net (code "152") (name "unconnected-(IC1-DIS-Pad7)") (class "Default")
      (node (ref "IC1") (pin "7") (pinfunction "DIS_7") (pintype "input"))
    )
    (net (code "153") (name "unconnected-(IC2-DIS-Pad7)") (class "Default")
      (node (ref "IC2") (pin "7") (pinfunction "DIS_7") (pintype "input"))
    )
    (net (code "154") (name "unconnected-(IC3-DIS-Pad7)") (class "Default")
      (node (ref "IC3") (pin "7") (pinfunction "DIS_7") (pintype "input"))
    )
    (net (code "155") (name "unconnected-(IC4-DIS-Pad7)") (class "Default")
      (node (ref "IC4") (pin "7") (pinfunction "DIS_7") (pintype "input"))
    )
    (net (code "156") (name "unconnected-(IC5-DIS-Pad7)") (class "Default")
      (node (ref "IC5") (pin "7") (pinfunction "DIS_7") (pintype "input"))
    )
    (net (code "157") (name "unconnected-(IC6-DIS-Pad7)") (class "Default")
      (node (ref "IC6") (pin "7") (pinfunction "DIS_7") (pintype "input"))
    )
    (net (code "158") (name "unconnected-(IC7-DIS-Pad7)") (class "Default")
      (node (ref "IC7") (pin "7") (pinfunction "DIS_7") (pintype "input"))
    )
    (net (code "159") (name "unconnected-(L2-Pad1)") (class "Default")
      (node (ref "L2") (pin "1") (pinfunction "1_1") (pintype "passive"))
    )
    (net (code "160") (name "unconnected-(L2-Pad2)") (class "Default")
      (node (ref "L2") (pin "2") (pinfunction "2_2") (pintype "passive"))
    )
    (net (code "161") (name "unconnected-(L4-Pad1)") (class "Default")
      (node (ref "L4") (pin "1") (pinfunction "1_1") (pintype "passive"))
    )
    (net (code "162") (name "unconnected-(L4-Pad2)") (class "Default")
      (node (ref "L4") (pin "2") (pinfunction "2_2") (pintype "passive"))
    )
    (net (code "163") (name "unconnected-(L6-Pad1)") (class "Default")
      (node (ref "L6") (pin "1") (pinfunction "1_1") (pintype "passive"))
    )
    (net (code "164") (name "unconnected-(L6-Pad2)") (class "Default")
      (node (ref "L6") (pin "2") (pinfunction "2_2") (pintype "passive"))
    )
    (net (code "165") (name "unconnected-(L8-Pad1)") (class "Default")
      (node (ref "L8") (pin "1") (pinfunction "1_1") (pintype "passive"))
    )
    (net (code "166") (name "unconnected-(L8-Pad2)") (class "Default")
      (node (ref "L8") (pin "2") (pinfunction "2_2") (pintype "passive"))
    )
    (net (code "167") (name "unconnected-(N1-Pad6)") (class "Default")
      (node (ref "N1") (pin "6") (pinfunction "6_6") (pintype "bidirectional"))
    )
    (net (code "168") (name "unconnected-(N1-Pad7)") (class "Default")
      (node (ref "N1") (pin "7") (pinfunction "7_7") (pintype "bidirectional"))
    )
    (net (code "169") (name "unconnected-(N1-Pad8)") (class "Default")
      (node (ref "N1") (pin "8") (pinfunction "8_8") (pintype "bidirectional"))
    )
    (net (code "170") (name "unconnected-(N1-Pad9)") (class "Default")
      (node (ref "N1") (pin "9") (pinfunction "9_9") (pintype "bidirectional"))
    )
    (net (code "171") (name "unconnected-(N3-Pad6)") (class "Default")
      (node (ref "N3") (pin "6") (pinfunction "6_6") (pintype "bidirectional"))
    )
    (net (code "172") (name "unconnected-(N3-Pad7)") (class "Default")
      (node (ref "N3") (pin "7") (pinfunction "7_7") (pintype "bidirectional"))
    )
    (net (code "173") (name "unconnected-(N3-Pad8)") (class "Default")
      (node (ref "N3") (pin "8") (pinfunction "8_8") (pintype "bidirectional"))
    )
    (net (code "174") (name "unconnected-(N3-Pad9)") (class "Default")
      (node (ref "N3") (pin "9") (pinfunction "9_9") (pintype "bidirectional"))
    )
    (net (code "175") (name "unconnected-(R2-Pad2)") (class "Default")
      (node (ref "R2") (pin "2") (pinfunction "2_2") (pintype "passive"))
    )
    (net (code "176") (name "unconnected-(R27-Pad2)") (class "Default")
      (node (ref "R27") (pin "2") (pinfunction "2_2") (pintype "passive"))
    )
    (net (code "177") (name "unconnected-(R30-Pad2)") (class "Default")
      (node (ref "R30") (pin "2") (pinfunction "2_2") (pintype "passive"))
    )
    (net (code "178") (name "unconnected-(R33-Pad2)") (class "Default")
      (node (ref "R33") (pin "2") (pinfunction "2_2") (pintype "passive"))
    )
    (net (code "179") (name "unconnected-(R36-Pad2)") (class "Default")
      (node (ref "R36") (pin "2") (pinfunction "2_2") (pintype "passive"))
    )
    (net (code "180") (name "unconnected-(R37-Pad2)") (class "Default")
      (node (ref "R37") (pin "2") (pinfunction "2_2") (pintype "passive"))
    )
    (net (code "181") (name "unconnected-(R39-Pad2)") (class "Default")
      (node (ref "R39") (pin "2") (pinfunction "2_2") (pintype "passive"))
    )
    (net (code "182") (name "unconnected-(R42-Pad2)") (class "Default")
      (node (ref "R42") (pin "2") (pinfunction "2_2") (pintype "passive"))
    )
    (net (code "183") (name "unconnected-(R54-Pad2)") (class "Default")
      (node (ref "R54") (pin "2") (pinfunction "2_2") (pintype "passive"))
    )
    (net (code "184") (name "unconnected-(T1-D2-Pad4)") (class "Default")
      (node (ref "T1") (pin "4") (pinfunction "D2_4") (pintype "passive"))
    )
    (net (code "185") (name "unconnected-(T4-D2-Pad4)") (class "Default")
      (node (ref "T4") (pin "4") (pinfunction "D2_4") (pintype "passive"))
    )
    (net (code "186") (name "unconnected-(T5-D2-Pad4)") (class "Default")
      (node (ref "T5") (pin "4") (pinfunction "D2_4") (pintype "passive"))
    )
    (net (code "187") (name "unconnected-(T6-D2-Pad4)") (class "Default")
      (node (ref "T6") (pin "4") (pinfunction "D2_4") (pintype "passive"))
    )
    (net (code "188") (name "unconnected-(T7-D2-Pad4)") (class "Default")
      (node (ref "T7") (pin "4") (pinfunction "D2_4") (pintype "passive"))
    )
    (net (code "189") (name "unconnected-(T8-D2-Pad4)") (class "Default")
      (node (ref "T8") (pin "4") (pinfunction "D2_4") (pintype "passive"))
    )
    (net (code "190") (name "unconnected-(T9-D2-Pad4)") (class "Default")
      (node (ref "T9") (pin "4") (pinfunction "D2_4") (pintype "passive"))
    )
    (net (code "191") (name "unconnected-(T10-D2-Pad4)") (class "Default")
      (node (ref "T10") (pin "4") (pinfunction "D2_4") (pintype "passive"))
    )
    (net (code "192") (name "unconnected-(T11-D2-Pad4)") (class "Default")
      (node (ref "T11") (pin "4") (pinfunction "D2_4") (pintype "passive"))
    )
    (net (code "193") (name "unconnected-(T12-D2-Pad4)") (class "Default")
      (node (ref "T12") (pin "4") (pinfunction "D2_4") (pintype "passive"))
    )
    (net (code "194") (name "unconnected-(T13-D2-Pad4)") (class "Default")
      (node (ref "T13") (pin "4") (pinfunction "D2_4") (pintype "passive"))
    )
    (net (code "195") (name "unconnected-(T14-D2-Pad4)") (class "Default")
      (node (ref "T14") (pin "4") (pinfunction "D2_4") (pintype "passive"))
    )
    (net (code "196") (name "unconnected-(U$3-0-Pad11)") (class "Default")
      (node (ref "U$3") (pin "11") (pinfunction "0_11") (pintype "bidirectional"))
    )
    (net (code "197") (name "unconnected-(U$3-A-Pad12)") (class "Default")
      (node (ref "U$3") (pin "12") (pinfunction "A_12") (pintype "bidirectional"))
    )
    (net (code "198") (name "unconnected-(U$3-Pad1)") (class "Default")
      (node (ref "U$3") (pin "1") (pinfunction "1_1") (pintype "bidirectional"))
    )
    (net (code "199") (name "unconnected-(U$3-Pad2)") (class "Default")
      (node (ref "U$3") (pin "2") (pinfunction "2_2") (pintype "bidirectional"))
    )
    (net (code "200") (name "unconnected-(U$3-Pad3)") (class "Default")
      (node (ref "U$3") (pin "3") (pinfunction "3_3") (pintype "bidirectional"))
    )
    (net (code "201") (name "unconnected-(U$3-Pad4)") (class "Default")
      (node (ref "U$3") (pin "4") (pinfunction "4_4") (pintype "bidirectional"))
    )
    (net (code "202") (name "unconnected-(U$3-Pad5)") (class "Default")
      (node (ref "U$3") (pin "5") (pinfunction "5_5") (pintype "bidirectional"))
    )
    (net (code "203") (name "unconnected-(U$7-0-Pad11)") (class "Default")
      (node (ref "U$7") (pin "11") (pinfunction "0_11") (pintype "bidirectional"))
    )
    (net (code "204") (name "unconnected-(U$7-A-Pad12)") (class "Default")
      (node (ref "U$7") (pin "12") (pinfunction "A_12") (pintype "bidirectional"))
    )
    (net (code "205") (name "unconnected-(U$7-Pad1)") (class "Default")
      (node (ref "U$7") (pin "1") (pinfunction "1_1") (pintype "bidirectional"))
    )
    (net (code "206") (name "unconnected-(U$7-Pad2)") (class "Default")
      (node (ref "U$7") (pin "2") (pinfunction "2_2") (pintype "bidirectional"))
    )
    (net (code "207") (name "unconnected-(U$7-Pad3)") (class "Default")
      (node (ref "U$7") (pin "3") (pinfunction "3_3") (pintype "bidirectional"))
    )
    (net (code "208") (name "unconnected-(U$7-Pad4)") (class "Default")
      (node (ref "U$7") (pin "4") (pinfunction "4_4") (pintype "bidirectional"))
    )
    (net (code "209") (name "unconnected-(U$7-Pad5)") (class "Default")
      (node (ref "U$7") (pin "5") (pinfunction "5_5") (pintype "bidirectional"))
    )
    (net (code "210") (name "unconnected-(U$10-0-Pad11)") (class "Default")
      (node (ref "U$10") (pin "11") (pinfunction "0_11") (pintype "bidirectional"))
    )
    (net (code "211") (name "unconnected-(U$10-A-Pad12)") (class "Default")
      (node (ref "U$10") (pin "12") (pinfunction "A_12") (pintype "bidirectional"))
    )
    (net (code "212") (name "unconnected-(U$10-Pad1)") (class "Default")
      (node (ref "U$10") (pin "1") (pinfunction "1_1") (pintype "bidirectional"))
    )
    (net (code "213") (name "unconnected-(U$10-Pad2)") (class "Default")
      (node (ref "U$10") (pin "2") (pinfunction "2_2") (pintype "bidirectional"))
    )
    (net (code "214") (name "unconnected-(U$10-Pad3)") (class "Default")
      (node (ref "U$10") (pin "3") (pinfunction "3_3") (pintype "bidirectional"))
    )
    (net (code "215") (name "unconnected-(U$10-Pad4)") (class "Default")
      (node (ref "U$10") (pin "4") (pinfunction "4_4") (pintype "bidirectional"))
    )
    (net (code "216") (name "unconnected-(U$10-Pad5)") (class "Default")
      (node (ref "U$10") (pin "5") (pinfunction "5_5") (pintype "bidirectional"))
    )
    (net (code "217") (name "unconnected-(U$11-0-Pad11)") (class "Default")
      (node (ref "U$11") (pin "11") (pinfunction "0_11") (pintype "bidirectional"))
    )
    (net (code "218") (name "unconnected-(U$11-A-Pad12)") (class "Default")
      (node (ref "U$11") (pin "12") (pinfunction "A_12") (pintype "bidirectional"))
    )
    (net (code "219") (name "unconnected-(U$11-Pad1)") (class "Default")
      (node (ref "U$11") (pin "1") (pinfunction "1_1") (pintype "bidirectional"))
    )
    (net (code "220") (name "unconnected-(U$11-Pad2)") (class "Default")
      (node (ref "U$11") (pin "2") (pinfunction "2_2") (pintype "bidirectional"))
    )
    (net (code "221") (name "unconnected-(U$11-Pad3)") (class "Default")
      (node (ref "U$11") (pin "3") (pinfunction "3_3") (pintype "bidirectional"))
    )
    (net (code "222") (name "unconnected-(U$11-Pad4)") (class "Default")
      (node (ref "U$11") (pin "4") (pinfunction "4_4") (pintype "bidirectional"))
    )
    (net (code "223") (name "unconnected-(U$11-Pad5)") (class "Default")
      (node (ref "U$11") (pin "5") (pinfunction "5_5") (pintype "bidirectional"))
    )
    (net (code "224") (name "unconnected-(X1-Pad2)") (class "Default")
      (node (ref "X1") (pin "2") (pinfunction "2_2") (pintype "passive"))
    )
    (net (code "225") (name "unconnected-(X1-Pad9)") (class "Default")
      (node (ref "X1") (pin "9") (pinfunction "9_9") (pintype "passive"))
    )
    (net (code "226") (name "unconnected-(X2-Pad2)") (class "Default")
      (node (ref "X2") (pin "2") (pinfunction "2_2") (pintype "passive"))
    )
    (net (code "227") (name "unconnected-(X2-Pad9)") (class "Default")
      (node (ref "X2") (pin "9") (pinfunction "9_9") (pintype "passive"))
    )
    (net (code "228") (name "unconnected-(X3-Pad2)") (class "Default")
      (node (ref "X3") (pin "2") (pinfunction "2_2") (pintype "passive"))
    )
    (net (code "229") (name "unconnected-(X3-Pad9)") (class "Default")
      (node (ref "X3") (pin "9") (pinfunction "9_9") (pintype "passive"))
    )
    (net (code "230") (name "unconnected-(X4-Pad2)") (class "Default")
      (node (ref "X4") (pin "2") (pinfunction "2_2") (pintype "passive"))
    )
    (net (code "231") (name "unconnected-(X4-Pad9)") (class "Default")
      (node (ref "X4") (pin "9") (pinfunction "9_9") (pintype "passive"))
    )
  )
)
